# SolidWorksModel.net
KiCad netlist of a schematic drawn in EAGLE
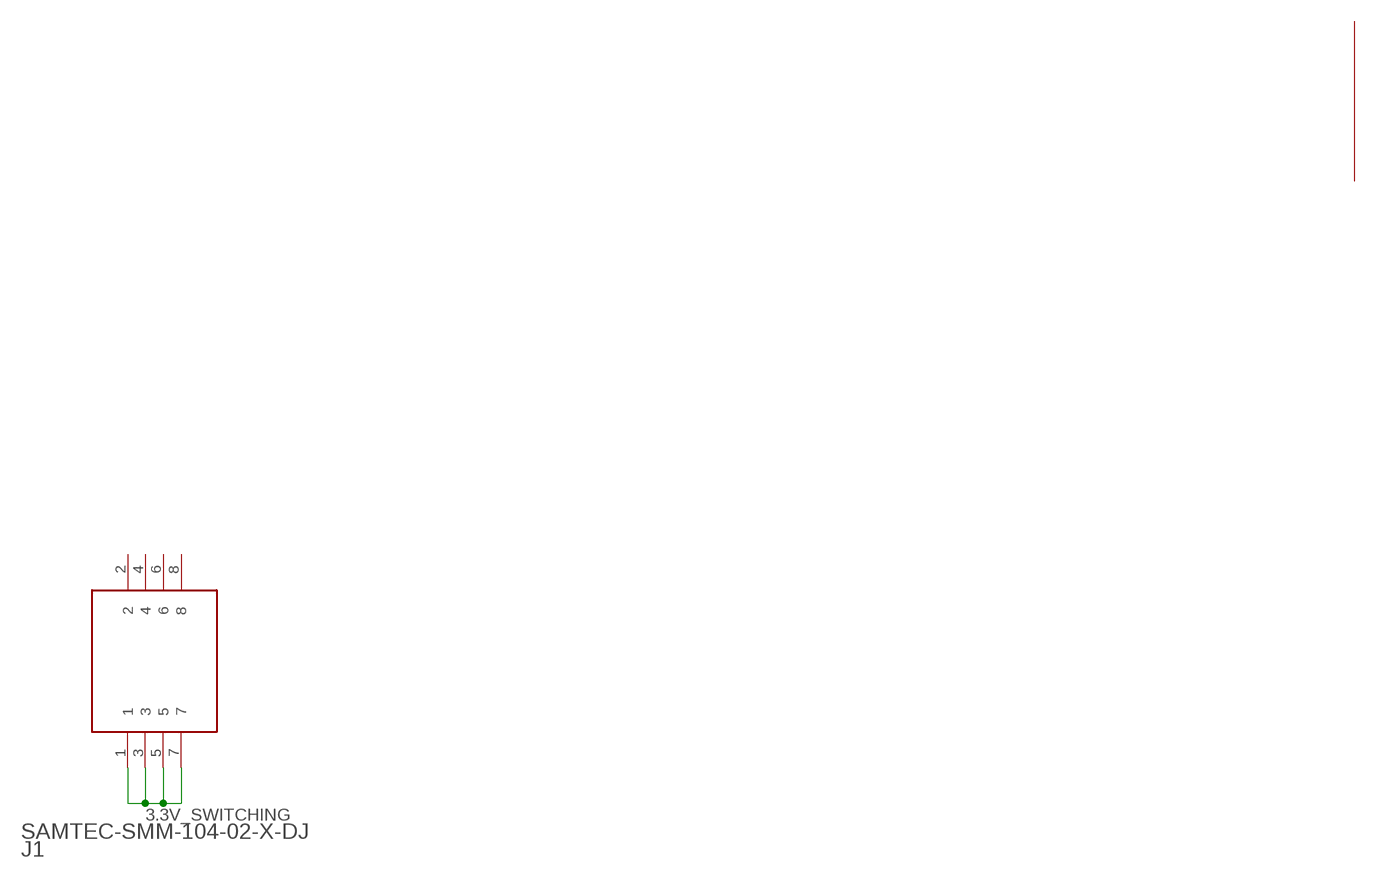
[diagram p0: schematic, sheet 3]
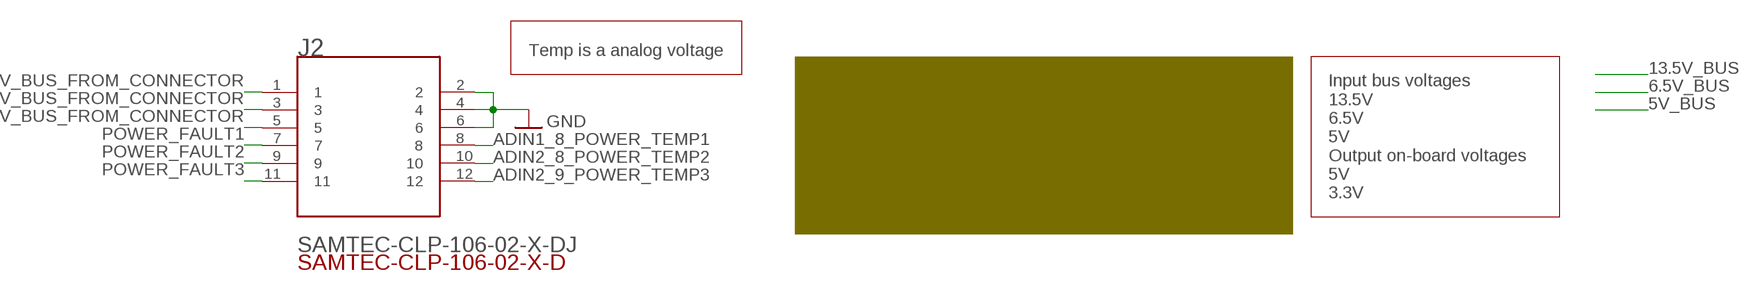
[diagram p1: schematic, sheet 4]
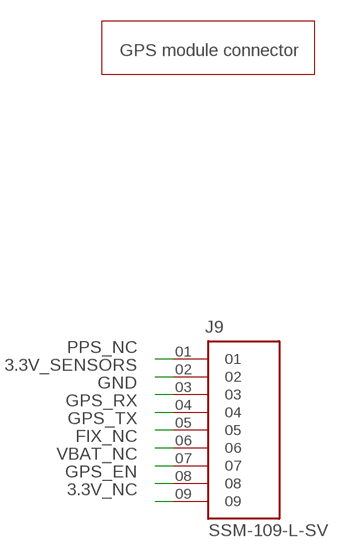
[diagram p2: schematic, sheet 7]
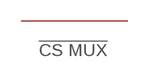
[diagram p3: schematic, sheet 10]
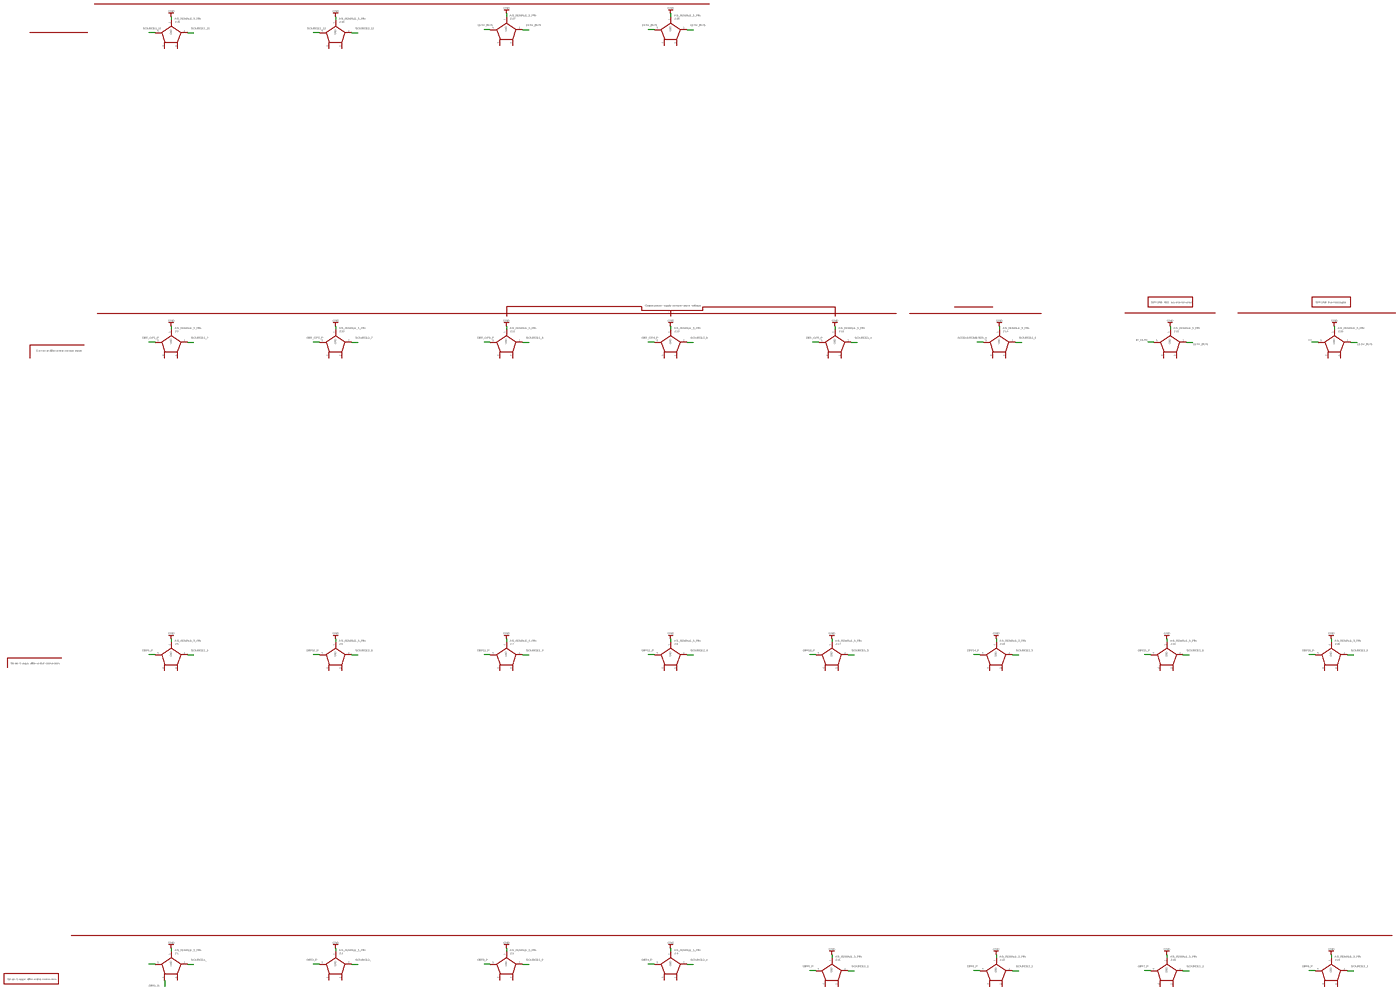
[diagram p4: schematic, sheet 11, overview]
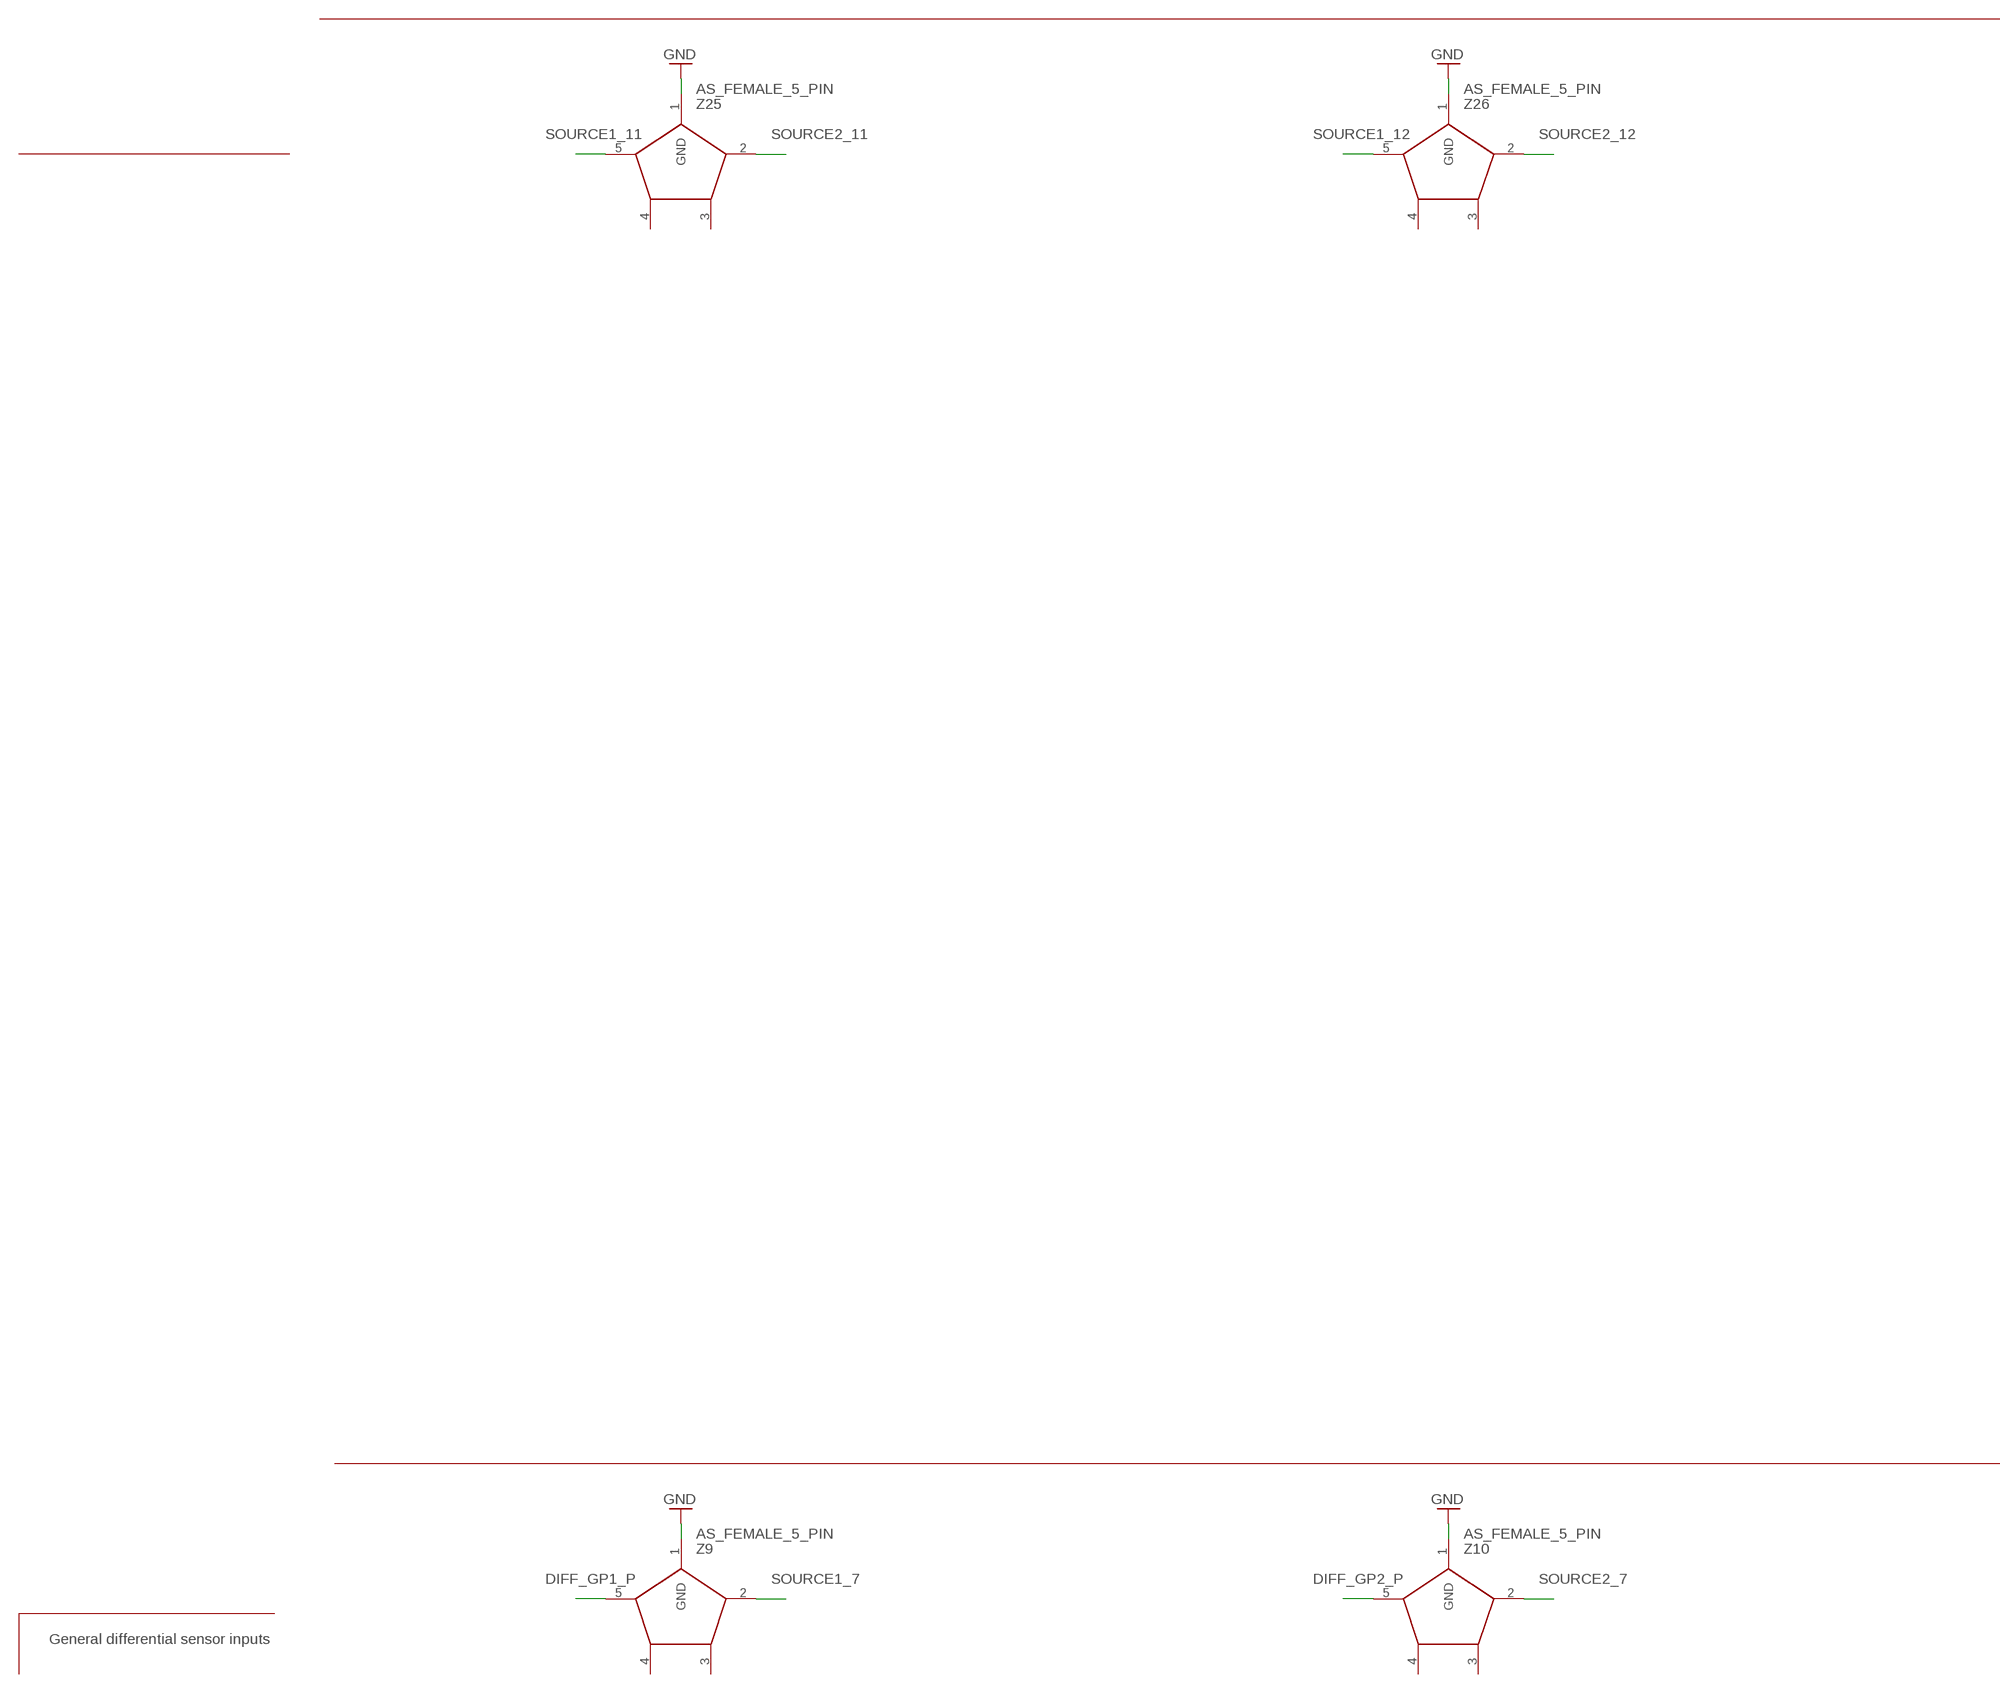
[diagram p5: schematic, sheet 11, part 1 of 6]
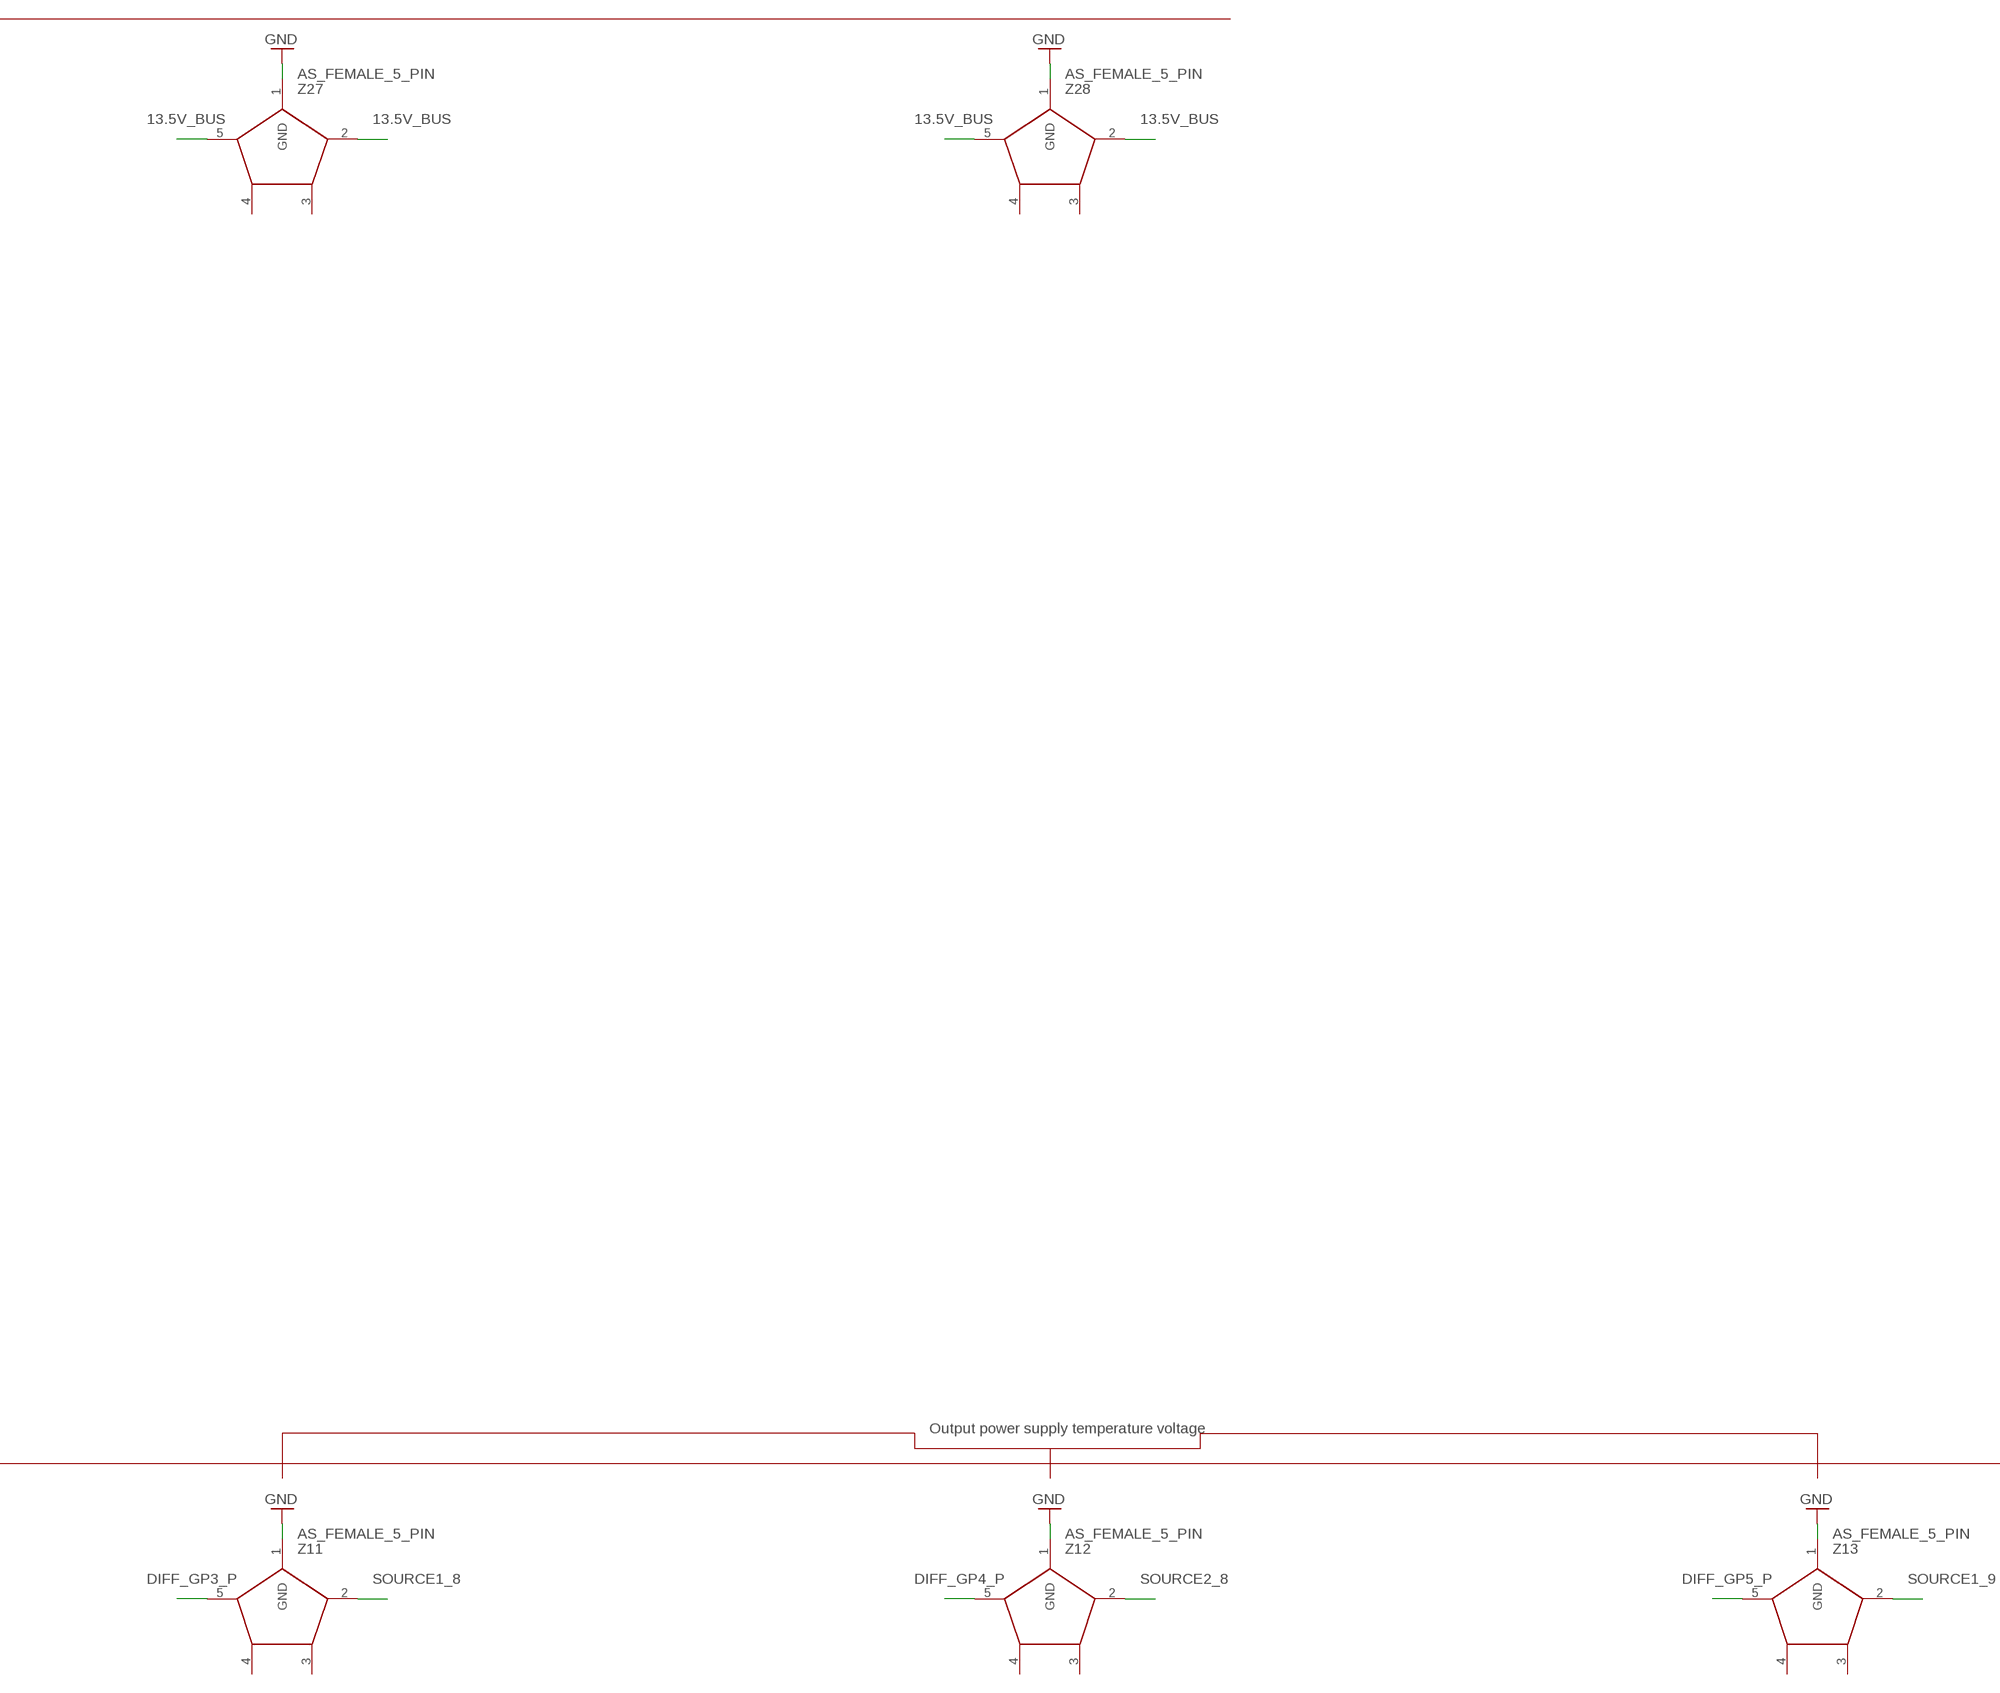
[diagram p6: schematic, sheet 11, part 2 of 6]
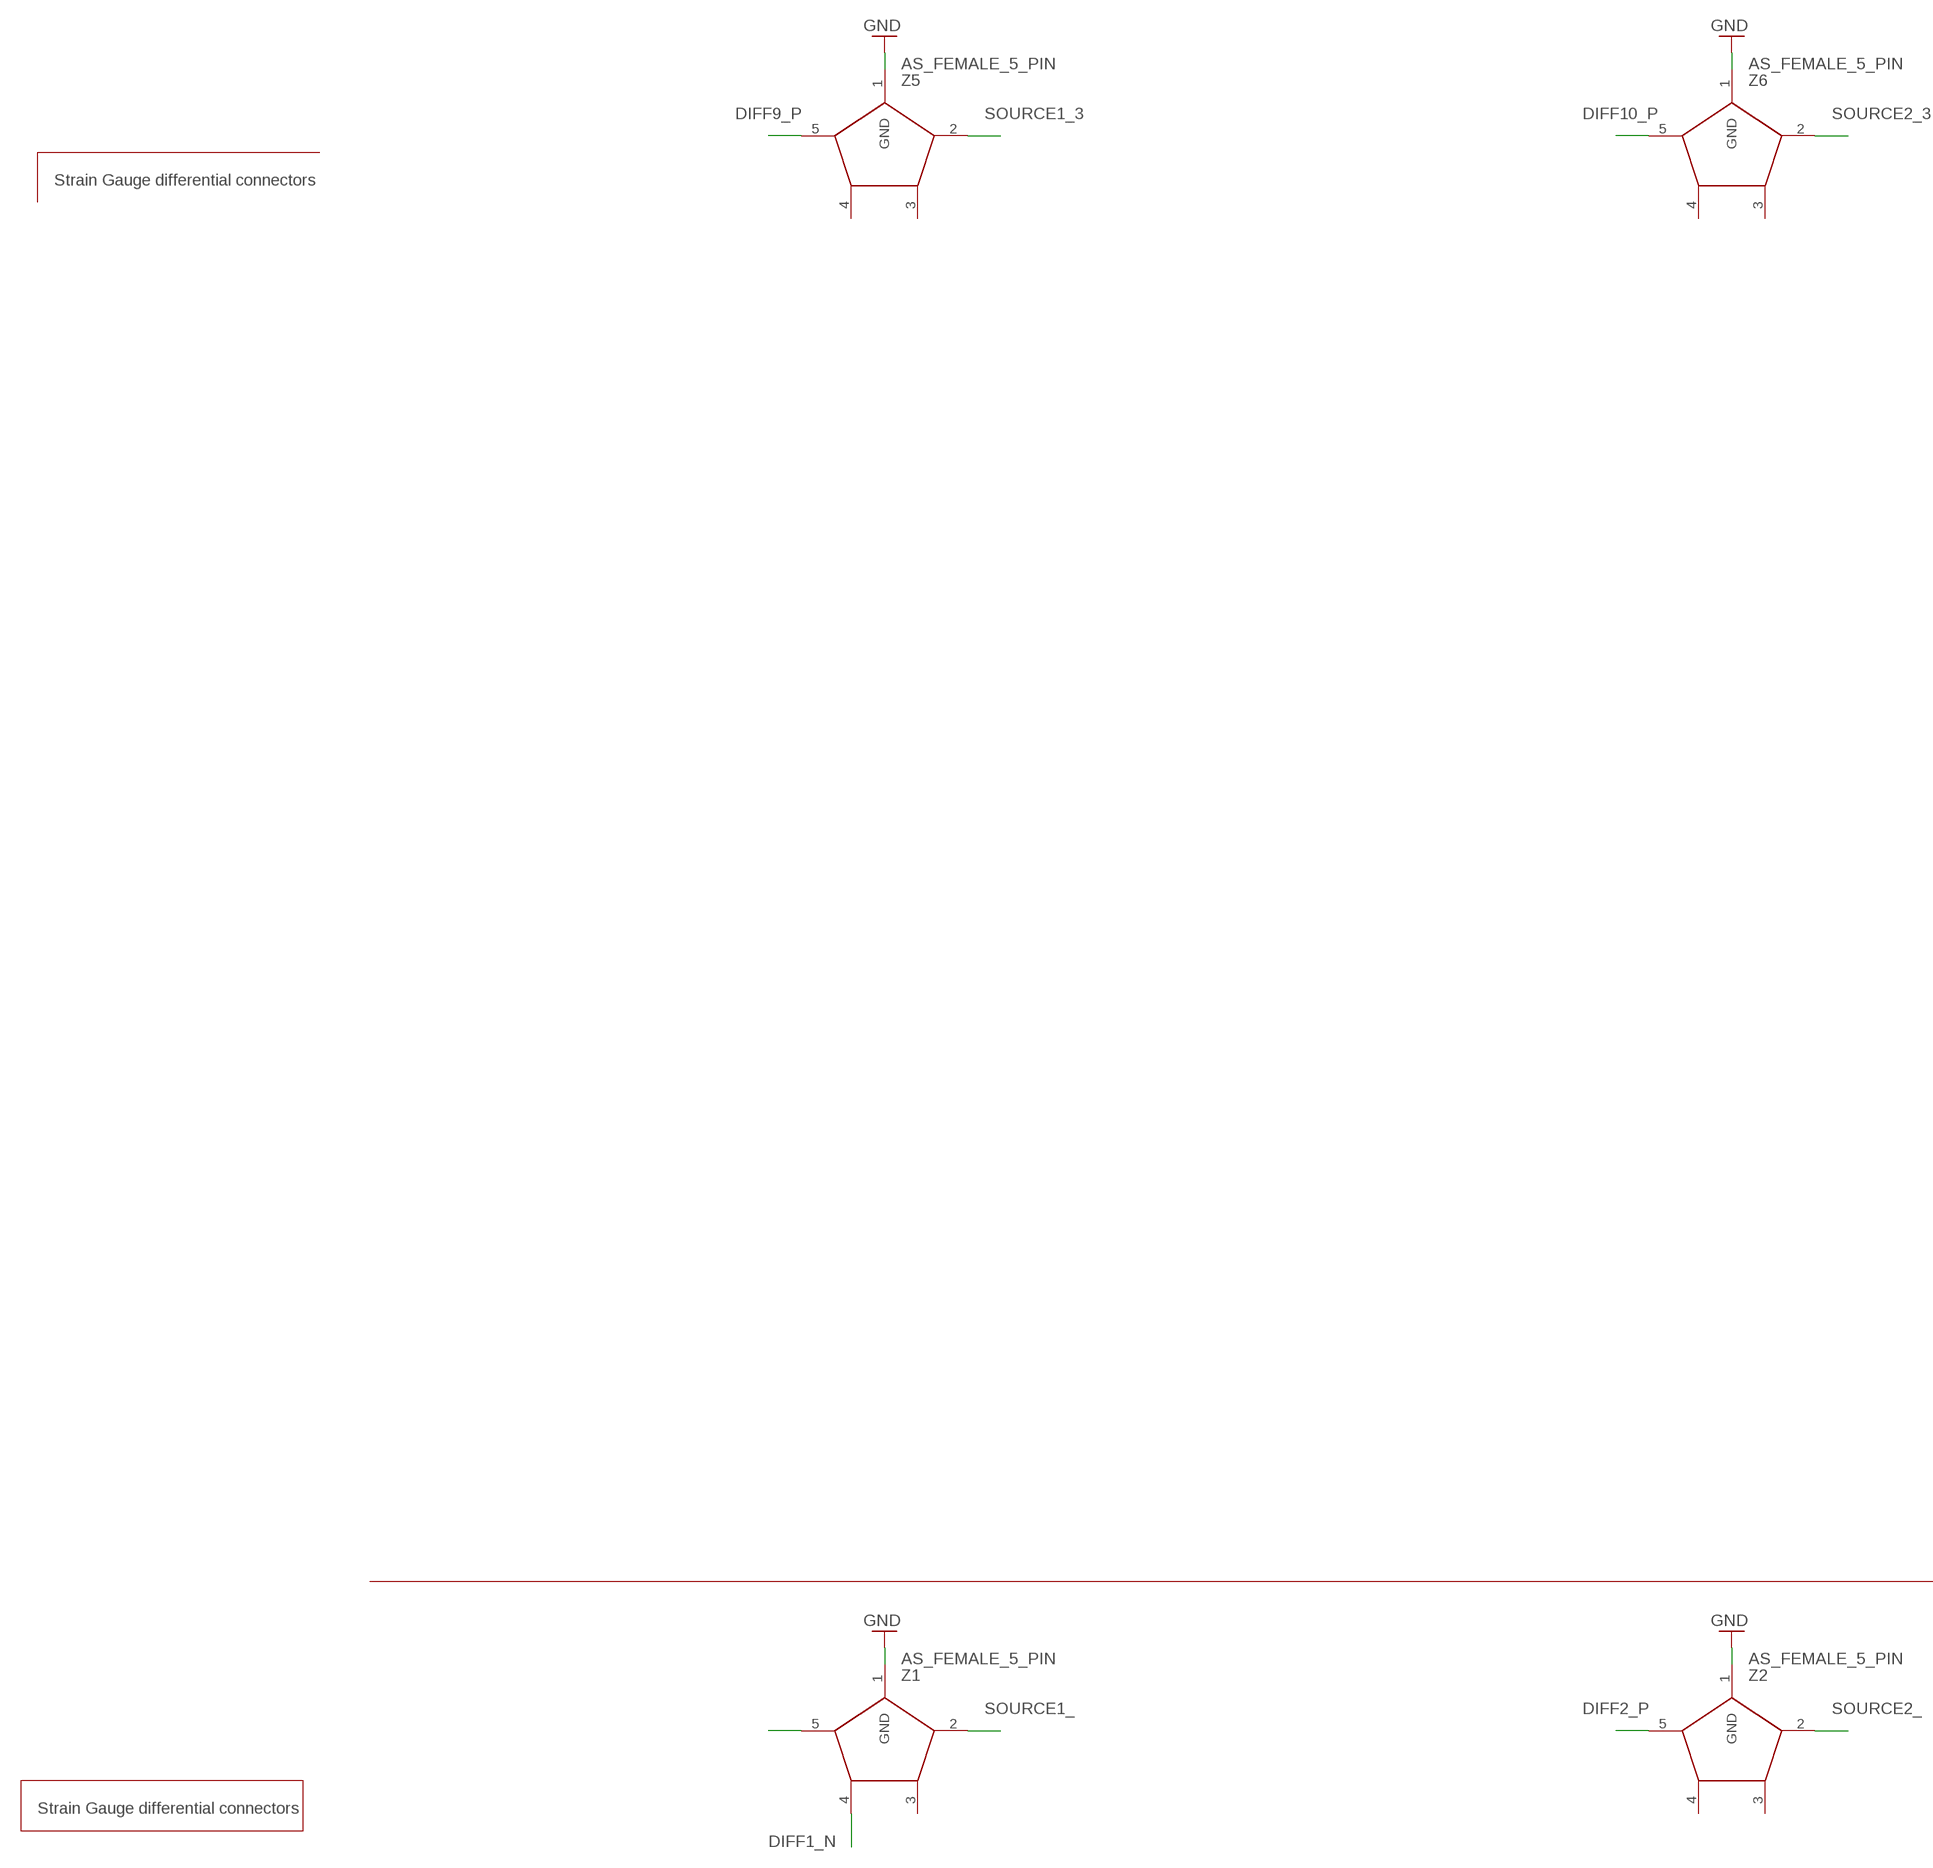
[diagram p7: schematic, sheet 11, part 3 of 6]
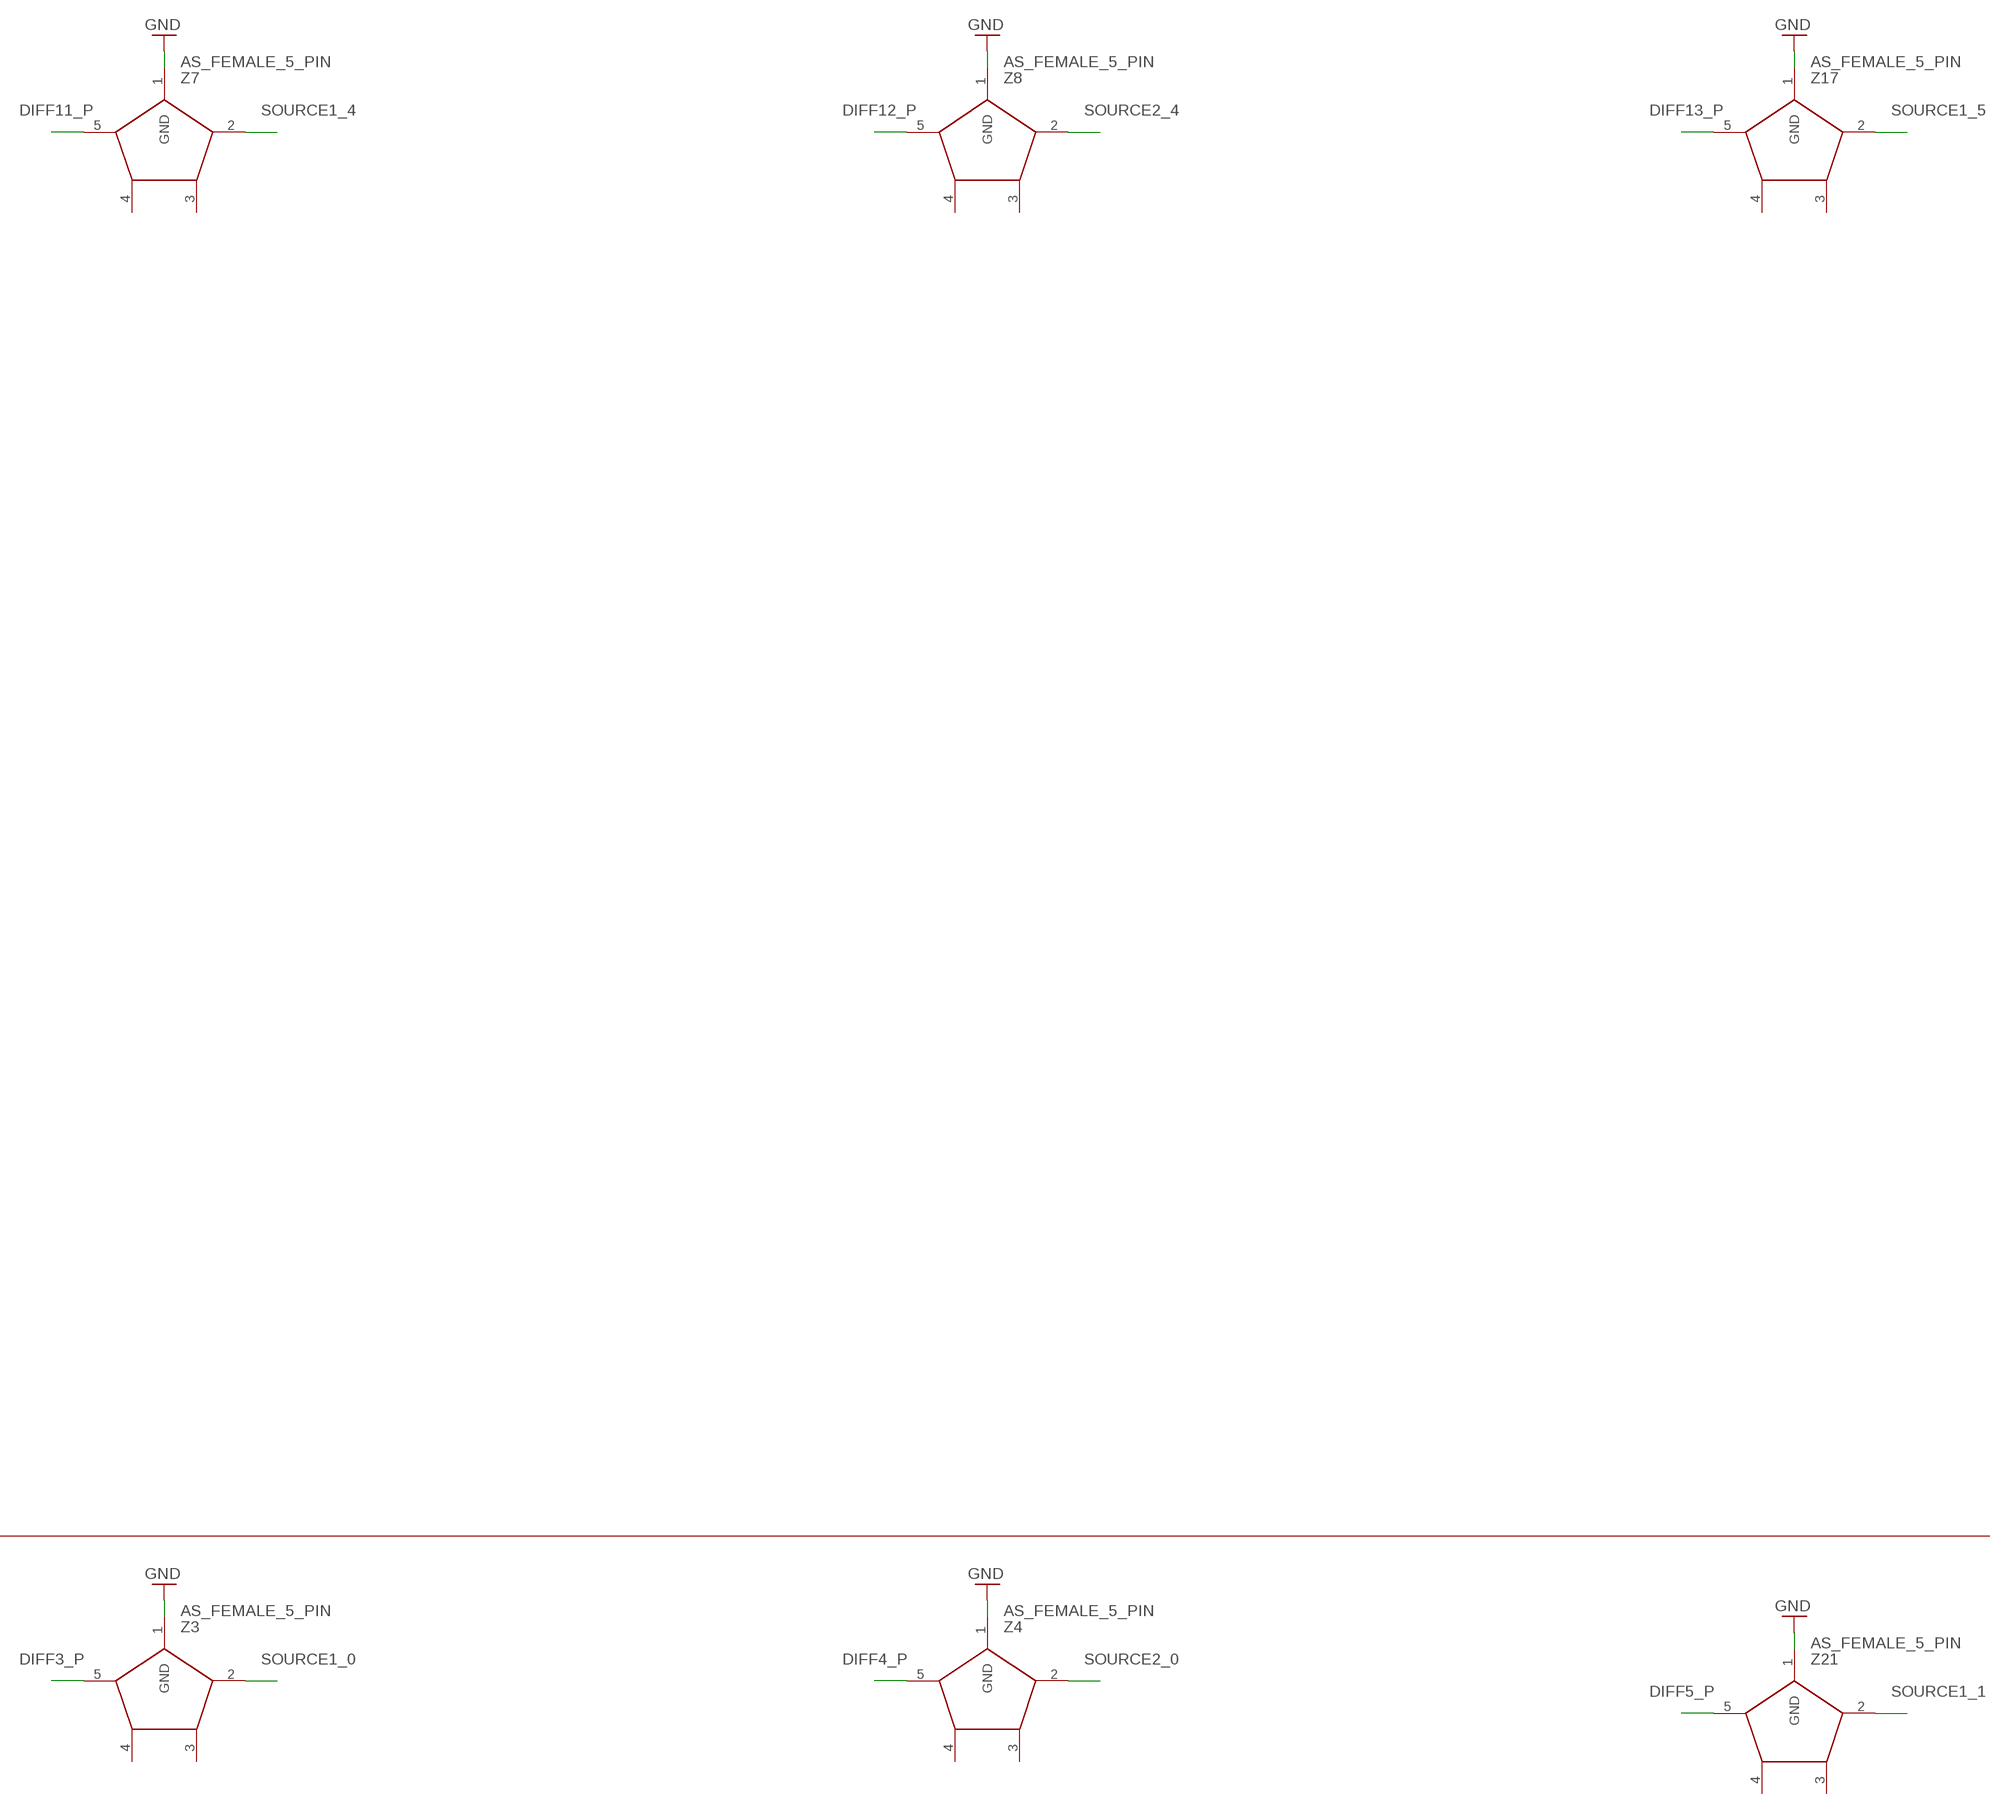
[diagram p8: schematic, sheet 11, part 4 of 6]
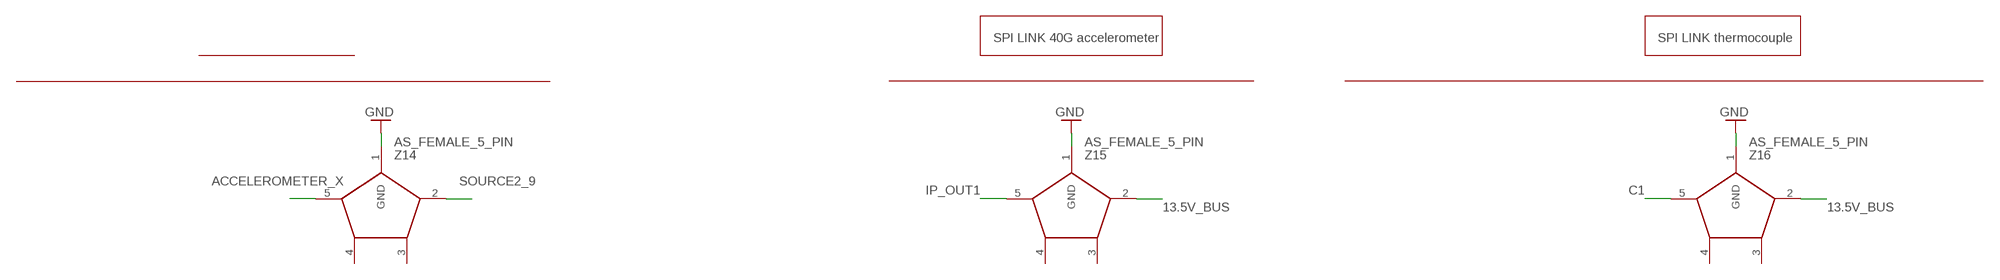
[diagram p9: schematic, sheet 11, part 5 of 6]
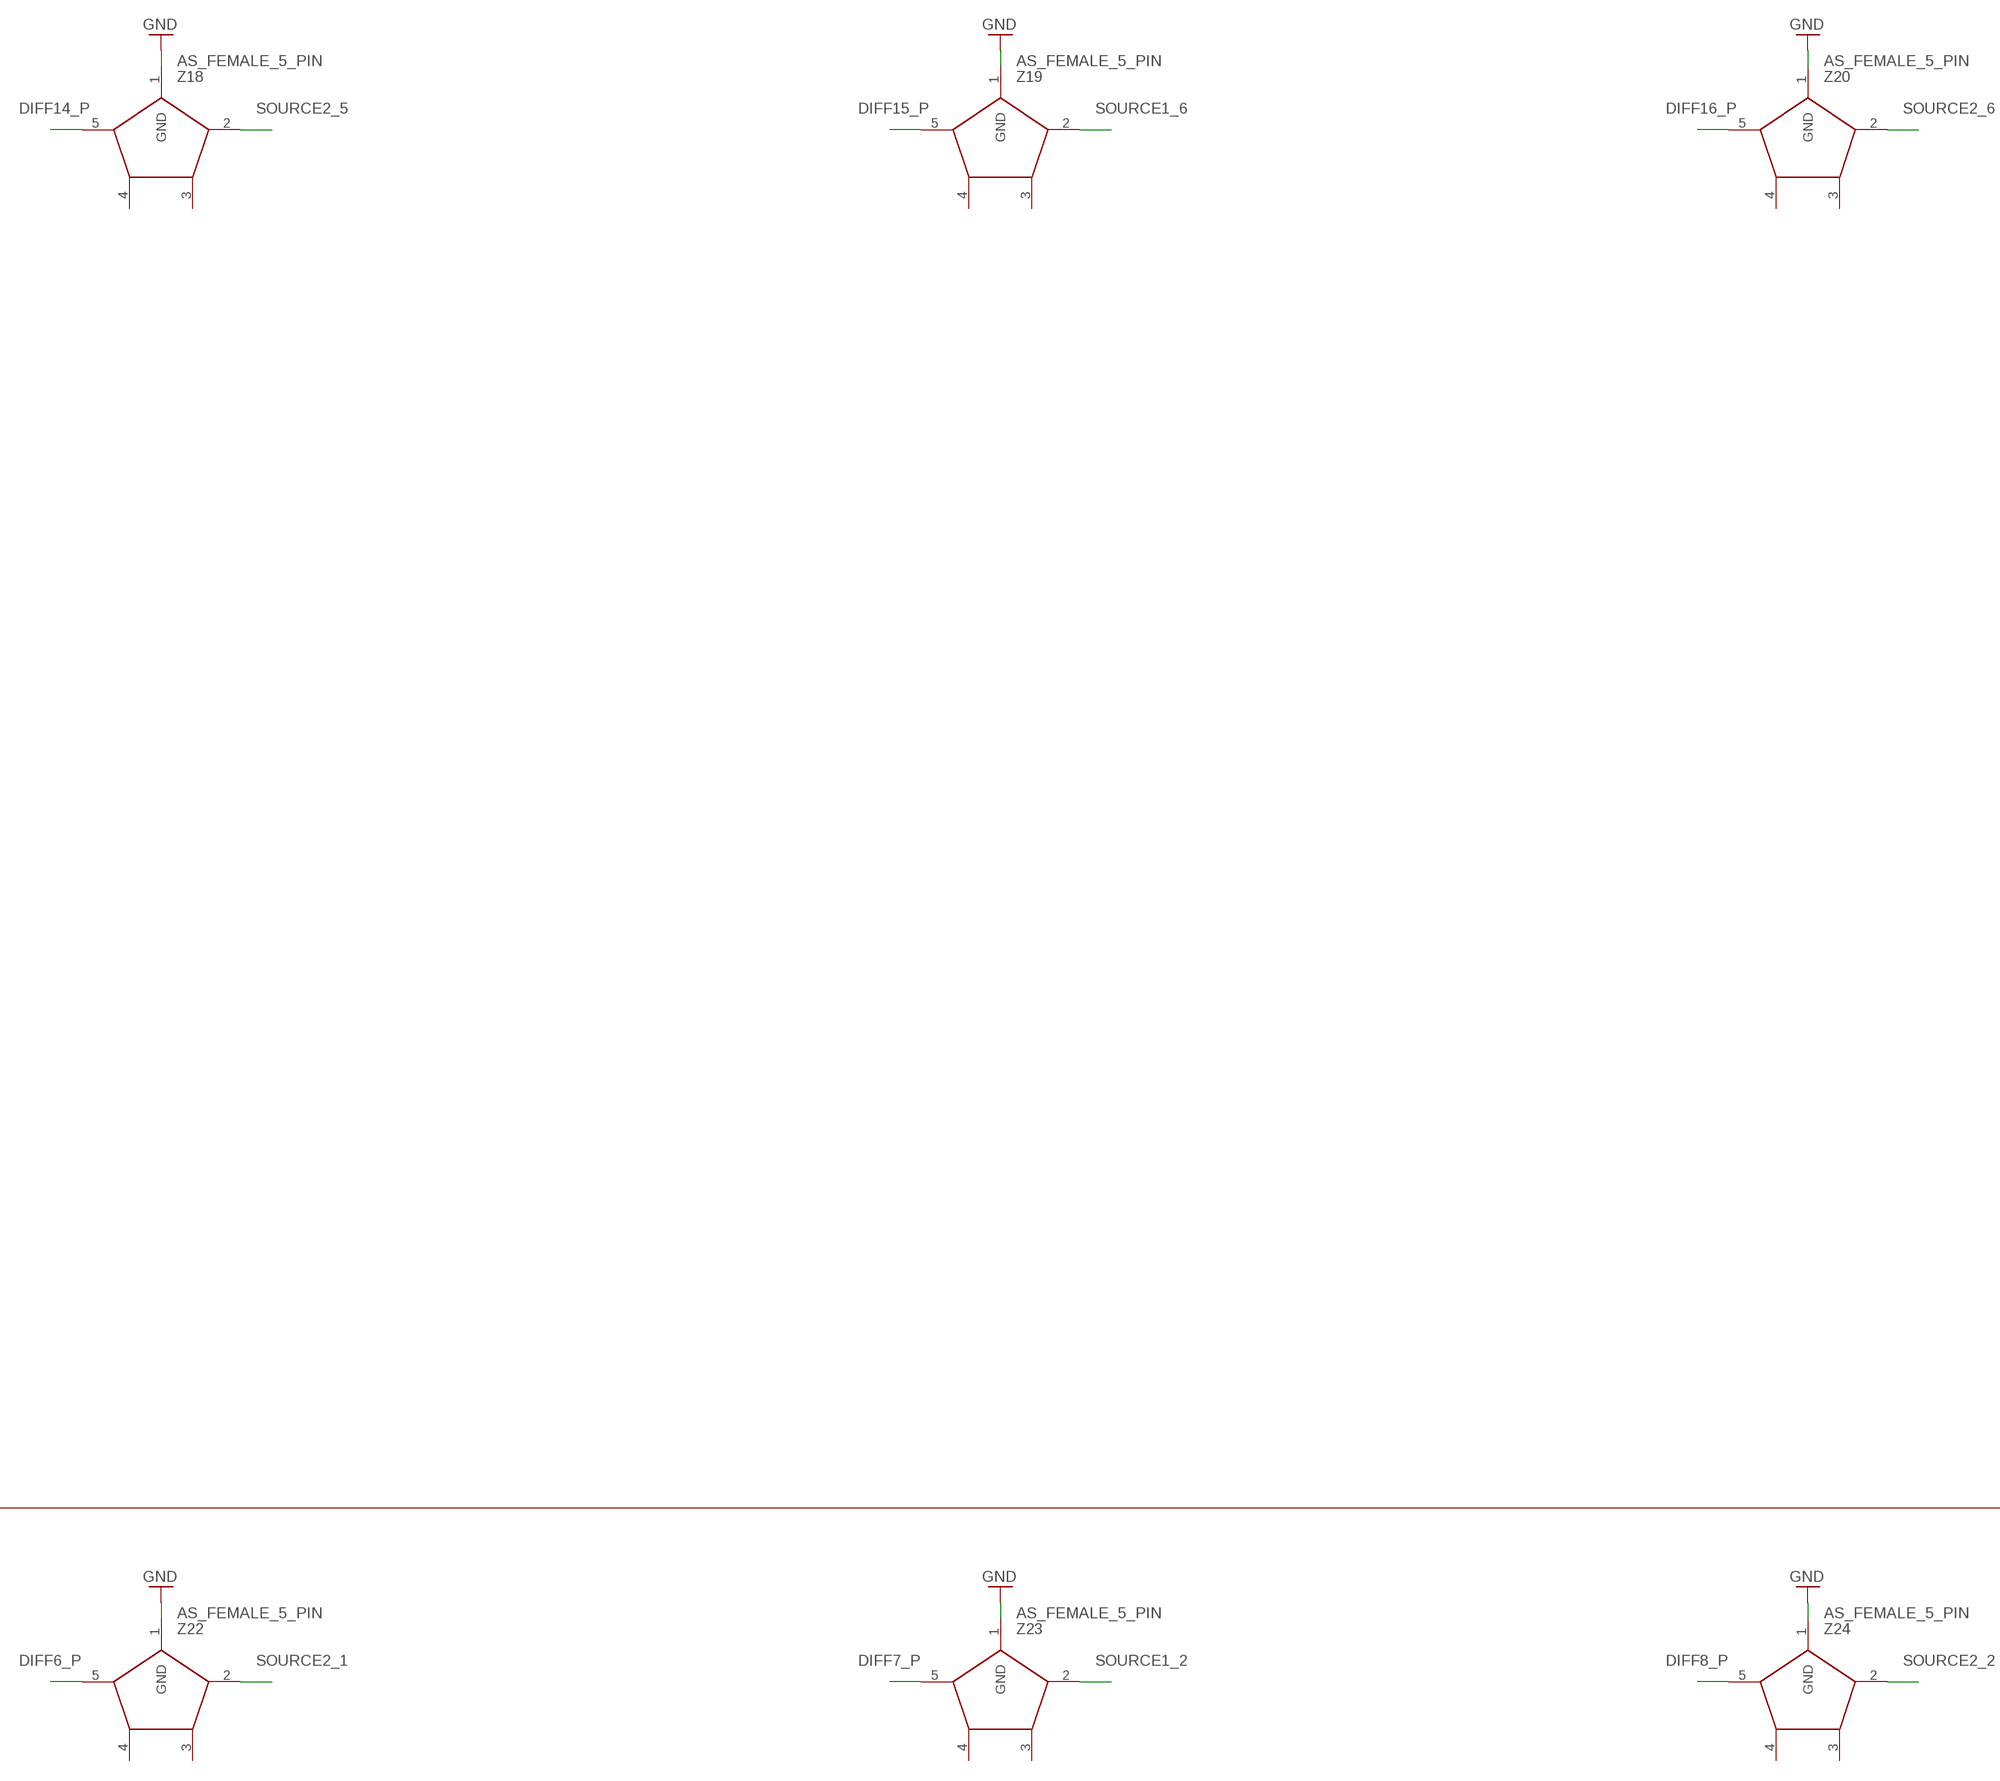
[diagram p10: schematic, sheet 11, part 6 of 6]
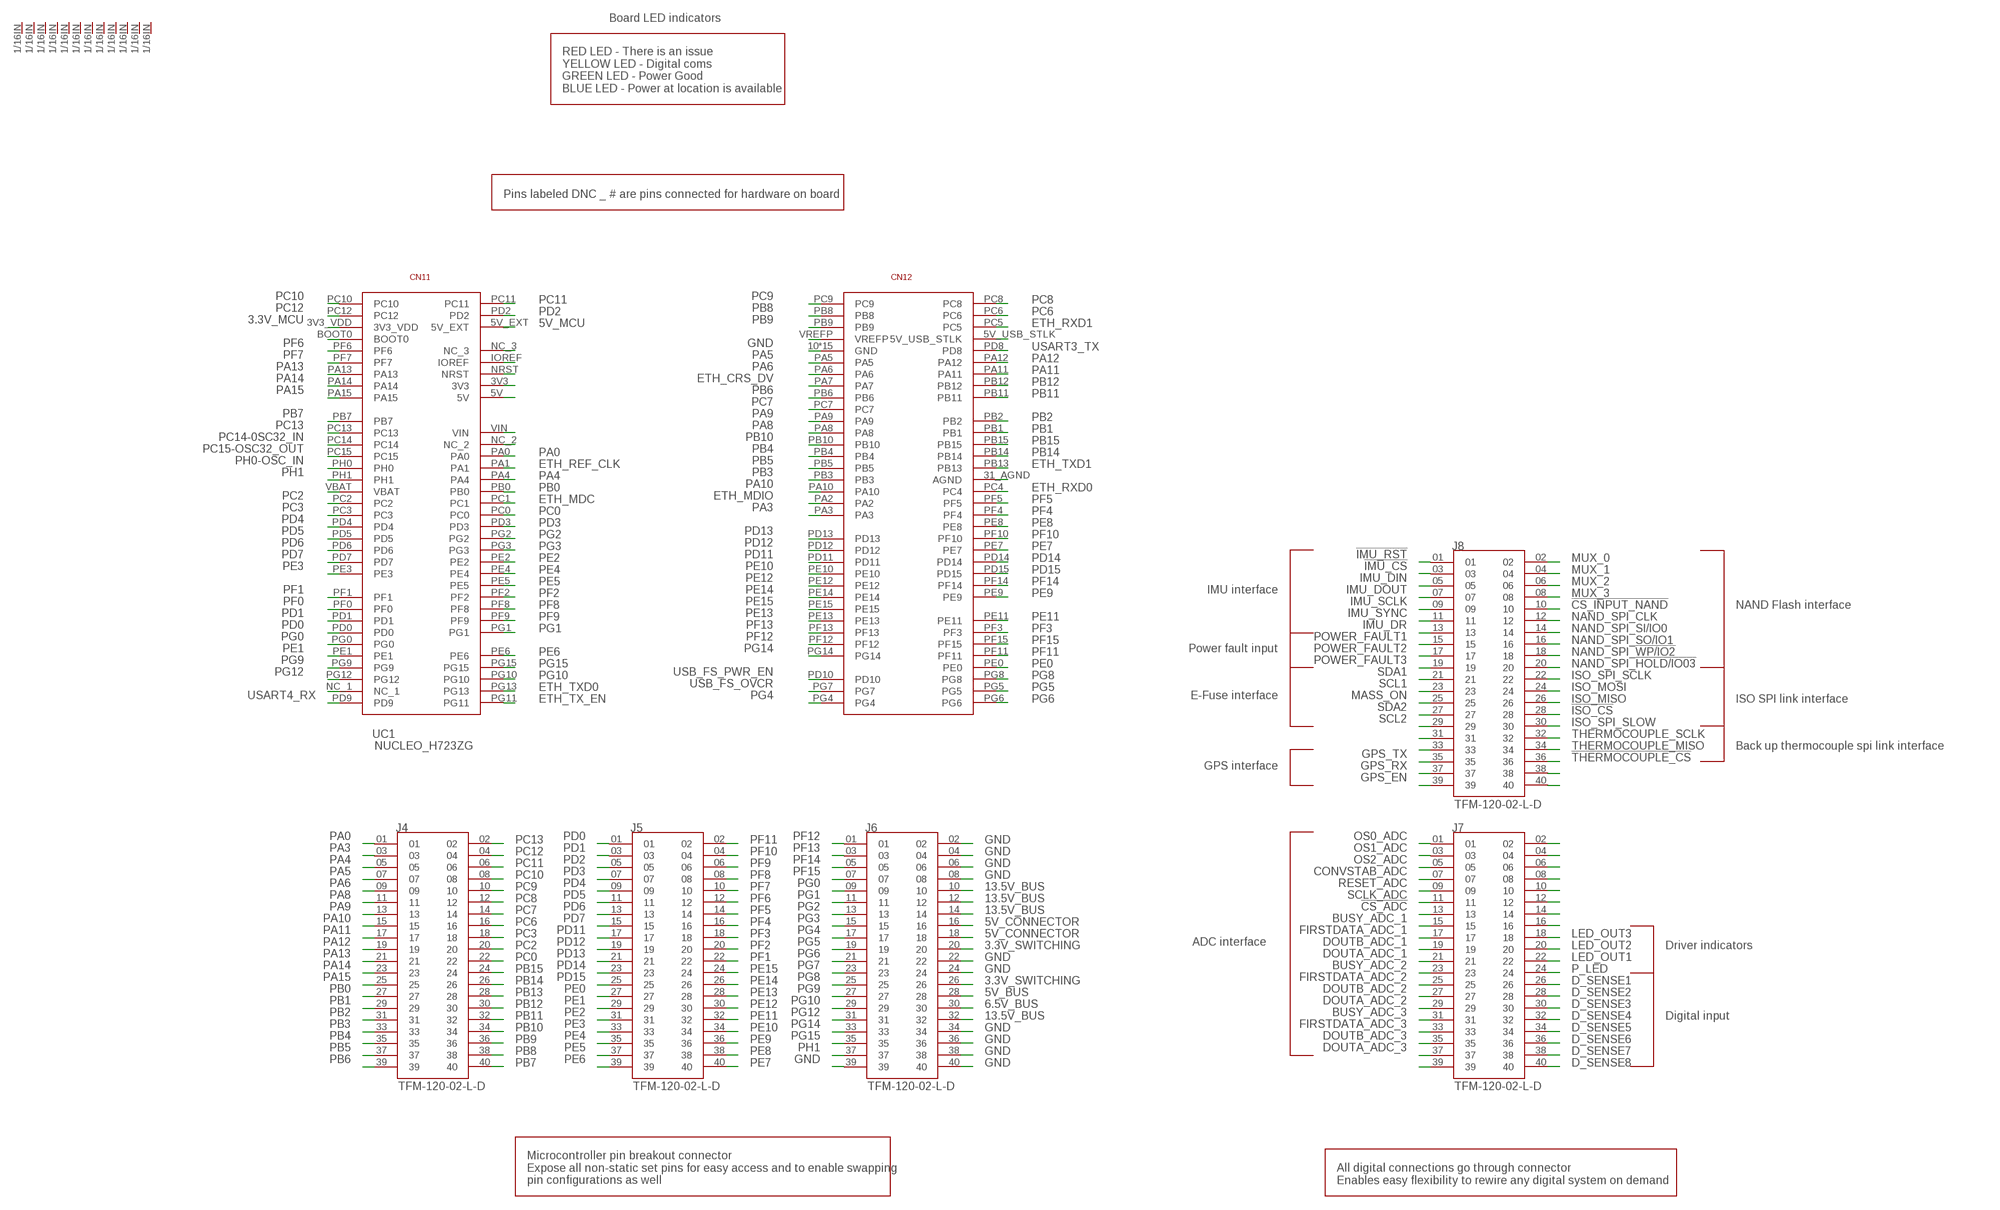
[diagram p11: schematic, sheet 12]

(export (version "E")
  (design (tool "Eeschema 10.0.6"))
  (components
    (comp (ref "J1")
      (value "SAMTEC-SMM-104-02-X-DJ")
      (footprint "eagle-import:SAMTEC-SMM-104-02-X-D")
      (libsource (lib "eagle-import") (part "SAMTEC-SMM-104-02-X-DJ"))
    )
    (comp (ref "J4")
      (value "TFM-120-02-L-D")
      (footprint "eagle-import:SAMTEC_TFM-120-02-L-D")
      (fields (field (name "MANUFACTURER") "Samtec"))
      (libsource (lib "eagle-import") (part "TFM-120-02-L-D"))
    )
    (comp (ref "J5")
      (value "TFM-120-02-L-D")
      (footprint "eagle-import:SAMTEC_TFM-120-02-L-D")
      (fields (field (name "MANUFACTURER") "Samtec"))
      (libsource (lib "eagle-import") (part "TFM-120-02-L-D"))
    )
    (comp (ref "J6")
      (value "TFM-120-02-L-D")
      (footprint "eagle-import:SAMTEC_TFM-120-02-L-D")
      (fields (field (name "MANUFACTURER") "Samtec"))
      (libsource (lib "eagle-import") (part "TFM-120-02-L-D"))
    )
    (comp (ref "J7")
      (value "TFM-120-02-L-D")
      (footprint "eagle-import:SAMTEC_TFM-120-02-L-D")
      (fields (field (name "MANUFACTURER") "Samtec"))
      (libsource (lib "eagle-import") (part "TFM-120-02-L-D"))
    )
    (comp (ref "J8")
      (value "TFM-120-02-L-D")
      (footprint "eagle-import:SAMTEC_TFM-120-02-L-D")
      (fields (field (name "MANUFACTURER") "Samtec"))
      (libsource (lib "eagle-import") (part "TFM-120-02-L-D"))
    )
    (comp (ref "U$1")
      (value "THROUGH_HOLE")
      (footprint "eagle-import:1_16TH_BOLT")
      (libsource (lib "eagle-import") (part "THROUGH_HOLE"))
    )
    (comp (ref "U$2")
      (value "THROUGH_HOLE")
      (footprint "eagle-import:1_16TH_BOLT")
      (libsource (lib "eagle-import") (part "THROUGH_HOLE"))
    )
    (comp (ref "U$3")
      (value "THROUGH_HOLE")
      (footprint "eagle-import:1_16TH_BOLT")
      (libsource (lib "eagle-import") (part "THROUGH_HOLE"))
    )
    (comp (ref "U$4")
      (value "THROUGH_HOLE")
      (footprint "eagle-import:1_16TH_BOLT")
      (libsource (lib "eagle-import") (part "THROUGH_HOLE"))
    )
    (comp (ref "U$5")
      (value "THROUGH_HOLE")
      (footprint "eagle-import:1_16TH_BOLT")
      (libsource (lib "eagle-import") (part "THROUGH_HOLE"))
    )
    (comp (ref "U$6")
      (value "THROUGH_HOLE")
      (footprint "eagle-import:1_16TH_BOLT")
      (libsource (lib "eagle-import") (part "THROUGH_HOLE"))
    )
    (comp (ref "U$7")
      (value "THROUGH_HOLE")
      (footprint "eagle-import:1_16TH_BOLT")
      (libsource (lib "eagle-import") (part "THROUGH_HOLE"))
    )
    (comp (ref "U$8")
      (value "THROUGH_HOLE")
      (footprint "eagle-import:1_16TH_BOLT")
      (libsource (lib "eagle-import") (part "THROUGH_HOLE"))
    )
    (comp (ref "U$9")
      (value "THROUGH_HOLE")
      (footprint "eagle-import:1_16TH_BOLT")
      (libsource (lib "eagle-import") (part "THROUGH_HOLE"))
    )
    (comp (ref "U$10")
      (value "THROUGH_HOLE")
      (footprint "eagle-import:1_16TH_BOLT")
      (libsource (lib "eagle-import") (part "THROUGH_HOLE"))
    )
    (comp (ref "U$11")
      (value "THROUGH_HOLE")
      (footprint "eagle-import:1_16TH_BOLT")
      (libsource (lib "eagle-import") (part "THROUGH_HOLE"))
    )
    (comp (ref "U$12")
      (value "THROUGH_HOLE")
      (footprint "eagle-import:1_16TH_BOLT")
      (libsource (lib "eagle-import") (part "THROUGH_HOLE"))
    )
    (comp (ref "UC1")
      (value "NUCLEO_H723ZG")
      (footprint "eagle-import:NUCLEO_H723ZG")
      (libsource (lib "eagle-import") (part "NUCLEO_H723ZG"))
    )
    (comp (ref "J2")
      (value "SAMTEC-CLP-106-02-X-DJ")
      (footprint "eagle-import:SAMTEC-CLP-106-02-X-D")
      (libsource (lib "eagle-import") (part "SAMTEC-CLP-106-02-X-DJ"))
    )
    (comp (ref "J9")
      (value "SSM-109-L-SV")
      (footprint "eagle-import:SAMTEC_SSM-109-L-SV")
      (fields (field (name "MANUFACTURER") "SAMTEC "))
      (libsource (lib "eagle-import") (part "SSM-109-L-SV"))
    )
    (comp (ref "Z1")
      (value "AS_FEMALE_5_PIN")
      (footprint "eagle-import:AS_FEMALE_5_PIN")
      (libsource (lib "eagle-import") (part "AS_FEMALE_5_PIN"))
    )
    (comp (ref "Z2")
      (value "AS_FEMALE_5_PIN")
      (footprint "eagle-import:AS_FEMALE_5_PIN")
      (libsource (lib "eagle-import") (part "AS_FEMALE_5_PIN"))
    )
    (comp (ref "Z3")
      (value "AS_FEMALE_5_PIN")
      (footprint "eagle-import:AS_FEMALE_5_PIN")
      (libsource (lib "eagle-import") (part "AS_FEMALE_5_PIN"))
    )
    (comp (ref "Z4")
      (value "AS_FEMALE_5_PIN")
      (footprint "eagle-import:AS_FEMALE_5_PIN")
      (libsource (lib "eagle-import") (part "AS_FEMALE_5_PIN"))
    )
    (comp (ref "Z5")
      (value "AS_FEMALE_5_PIN")
      (footprint "eagle-import:AS_FEMALE_5_PIN")
      (libsource (lib "eagle-import") (part "AS_FEMALE_5_PIN"))
    )
    (comp (ref "Z6")
      (value "AS_FEMALE_5_PIN")
      (footprint "eagle-import:AS_FEMALE_5_PIN")
      (libsource (lib "eagle-import") (part "AS_FEMALE_5_PIN"))
    )
    (comp (ref "Z7")
      (value "AS_FEMALE_5_PIN")
      (footprint "eagle-import:AS_FEMALE_5_PIN")
      (libsource (lib "eagle-import") (part "AS_FEMALE_5_PIN"))
    )
    (comp (ref "Z8")
      (value "AS_FEMALE_5_PIN")
      (footprint "eagle-import:AS_FEMALE_5_PIN")
      (libsource (lib "eagle-import") (part "AS_FEMALE_5_PIN"))
    )
    (comp (ref "Z9")
      (value "AS_FEMALE_5_PIN")
      (footprint "eagle-import:AS_FEMALE_5_PIN")
      (libsource (lib "eagle-import") (part "AS_FEMALE_5_PIN"))
    )
    (comp (ref "Z10")
      (value "AS_FEMALE_5_PIN")
      (footprint "eagle-import:AS_FEMALE_5_PIN")
      (libsource (lib "eagle-import") (part "AS_FEMALE_5_PIN"))
    )
    (comp (ref "Z11")
      (value "AS_FEMALE_5_PIN")
      (footprint "eagle-import:AS_FEMALE_5_PIN")
      (libsource (lib "eagle-import") (part "AS_FEMALE_5_PIN"))
    )
    (comp (ref "Z12")
      (value "AS_FEMALE_5_PIN")
      (footprint "eagle-import:AS_FEMALE_5_PIN")
      (libsource (lib "eagle-import") (part "AS_FEMALE_5_PIN"))
    )
    (comp (ref "Z13")
      (value "AS_FEMALE_5_PIN")
      (footprint "eagle-import:AS_FEMALE_5_PIN")
      (libsource (lib "eagle-import") (part "AS_FEMALE_5_PIN"))
    )
    (comp (ref "Z14")
      (value "AS_FEMALE_5_PIN")
      (footprint "eagle-import:AS_FEMALE_5_PIN")
      (libsource (lib "eagle-import") (part "AS_FEMALE_5_PIN"))
    )
    (comp (ref "Z15")
      (value "AS_FEMALE_5_PIN")
      (footprint "eagle-import:AS_FEMALE_5_PIN")
      (libsource (lib "eagle-import") (part "AS_FEMALE_5_PIN"))
    )
    (comp (ref "Z16")
      (value "AS_FEMALE_5_PIN")
      (footprint "eagle-import:AS_FEMALE_5_PIN")
      (libsource (lib "eagle-import") (part "AS_FEMALE_5_PIN"))
    )
    (comp (ref "Z17")
      (value "AS_FEMALE_5_PIN")
      (footprint "eagle-import:AS_FEMALE_5_PIN")
      (libsource (lib "eagle-import") (part "AS_FEMALE_5_PIN"))
    )
    (comp (ref "Z18")
      (value "AS_FEMALE_5_PIN")
      (footprint "eagle-import:AS_FEMALE_5_PIN")
      (libsource (lib "eagle-import") (part "AS_FEMALE_5_PIN"))
    )
    (comp (ref "Z19")
      (value "AS_FEMALE_5_PIN")
      (footprint "eagle-import:AS_FEMALE_5_PIN")
      (libsource (lib "eagle-import") (part "AS_FEMALE_5_PIN"))
    )
    (comp (ref "Z20")
      (value "AS_FEMALE_5_PIN")
      (footprint "eagle-import:AS_FEMALE_5_PIN")
      (libsource (lib "eagle-import") (part "AS_FEMALE_5_PIN"))
    )
    (comp (ref "Z21")
      (value "AS_FEMALE_5_PIN")
      (footprint "eagle-import:AS_FEMALE_5_PIN")
      (libsource (lib "eagle-import") (part "AS_FEMALE_5_PIN"))
    )
    (comp (ref "Z22")
      (value "AS_FEMALE_5_PIN")
      (footprint "eagle-import:AS_FEMALE_5_PIN")
      (libsource (lib "eagle-import") (part "AS_FEMALE_5_PIN"))
    )
    (comp (ref "Z23")
      (value "AS_FEMALE_5_PIN")
      (footprint "eagle-import:AS_FEMALE_5_PIN")
      (libsource (lib "eagle-import") (part "AS_FEMALE_5_PIN"))
    )
    (comp (ref "Z24")
      (value "AS_FEMALE_5_PIN")
      (footprint "eagle-import:AS_FEMALE_5_PIN")
      (libsource (lib "eagle-import") (part "AS_FEMALE_5_PIN"))
    )
    (comp (ref "Z25")
      (value "AS_FEMALE_5_PIN")
      (footprint "eagle-import:AS_FEMALE_5_PIN")
      (libsource (lib "eagle-import") (part "AS_FEMALE_5_PIN"))
    )
    (comp (ref "Z26")
      (value "AS_FEMALE_5_PIN")
      (footprint "eagle-import:AS_FEMALE_5_PIN")
      (libsource (lib "eagle-import") (part "AS_FEMALE_5_PIN"))
    )
    (comp (ref "Z27")
      (value "AS_FEMALE_5_PIN")
      (footprint "eagle-import:AS_FEMALE_5_PIN")
      (libsource (lib "eagle-import") (part "AS_FEMALE_5_PIN"))
    )
    (comp (ref "Z28")
      (value "AS_FEMALE_5_PIN")
      (footprint "eagle-import:AS_FEMALE_5_PIN")
      (libsource (lib "eagle-import") (part "AS_FEMALE_5_PIN"))
    )
  )
  (nets
    (net (code "1") (name "3.3V_MCU") (class "Default")
      (node (ref "UC1") (pin "3V3_VDD") (pinfunction "3V3_VDD_3V3_VDD") (pintype "passive"))
    )
    (net (code "2") (name "3.3V_NC") (class "Default")
      (node (ref "J9") (pin "09") (pinfunction "09_09") (pintype "passive"))
    )
    (net (code "3") (name "3.3V_SENSORS") (class "Default")
      (node (ref "J9") (pin "02") (pinfunction "02_02") (pintype "passive"))
    )
    (net (code "4") (name "3.3V_SWITCHING") (class "Default")
      (node (ref "J1") (pin "1") (pinfunction "1_1") (pintype "passive"))
      (node (ref "J1") (pin "3") (pinfunction "3_3") (pintype "passive"))
      (node (ref "J1") (pin "5") (pinfunction "5_5") (pintype "passive"))
      (node (ref "J1") (pin "7") (pinfunction "7_7") (pintype "passive"))
      (node (ref "J6") (pin "20") (pinfunction "20_20") (pintype "passive"))
      (node (ref "J6") (pin "26") (pinfunction "26_26") (pintype "passive"))
    )
    (net (code "5") (name "5V_BUS") (class "Default")
      (node (ref "J6") (pin "28") (pinfunction "28_28") (pintype "passive"))
    )
    (net (code "6") (name "5V_BUS_FROM_CONNECTOR") (class "Default")
      (node (ref "J2") (pin "5") (pinfunction "5_5") (pintype "passive"))
    )
    (net (code "7") (name "5V_CONNECTOR") (class "Default")
      (node (ref "J6") (pin "16") (pinfunction "16_16") (pintype "passive"))
      (node (ref "J6") (pin "18") (pinfunction "18_18") (pintype "passive"))
    )
    (net (code "8") (name "5V_MCU") (class "Default")
      (node (ref "UC1") (pin "5V_EXT") (pinfunction "5V_EXT_5V_EXT") (pintype "passive"))
    )
    (net (code "9") (name "6.5V_BUS") (class "Default")
      (node (ref "J6") (pin "30") (pinfunction "30_30") (pintype "passive"))
    )
    (net (code "10") (name "6.5V_BUS_FROM_CONNECTOR") (class "Default")
      (node (ref "J2") (pin "3") (pinfunction "3_3") (pintype "passive"))
    )
    (net (code "11") (name "13.5V_BUS") (class "Default")
      (node (ref "J6") (pin "10") (pinfunction "10_10") (pintype "passive"))
      (node (ref "J6") (pin "12") (pinfunction "12_12") (pintype "passive"))
      (node (ref "J6") (pin "14") (pinfunction "14_14") (pintype "passive"))
      (node (ref "J6") (pin "32") (pinfunction "32_32") (pintype "passive"))
      (node (ref "Z15") (pin "2") (pinfunction "1_2") (pintype "bidirectional"))
      (node (ref "Z16") (pin "2") (pinfunction "1_2") (pintype "bidirectional"))
      (node (ref "Z27") (pin "2") (pinfunction "1_2") (pintype "bidirectional"))
      (node (ref "Z27") (pin "5") (pinfunction "4_5") (pintype "bidirectional"))
      (node (ref "Z28") (pin "2") (pinfunction "1_2") (pintype "bidirectional"))
      (node (ref "Z28") (pin "5") (pinfunction "4_5") (pintype "bidirectional"))
    )
    (net (code "12") (name "14V_BUS_FROM_CONNECTOR") (class "Default")
      (node (ref "J2") (pin "1") (pinfunction "1_1") (pintype "passive"))
    )
    (net (code "13") (name "ACCELEROMETER_X") (class "Default")
      (node (ref "Z14") (pin "5") (pinfunction "4_5") (pintype "bidirectional"))
    )
    (net (code "14") (name "ADIN1_8_POWER_TEMP1") (class "Default")
      (node (ref "J2") (pin "8") (pinfunction "8_8") (pintype "passive"))
    )
    (net (code "15") (name "ADIN2_8_POWER_TEMP2") (class "Default")
      (node (ref "J2") (pin "10") (pinfunction "10_10") (pintype "passive"))
    )
    (net (code "16") (name "ADIN2_9_POWER_TEMP3") (class "Default")
      (node (ref "J2") (pin "12") (pinfunction "12_12") (pintype "passive"))
    )
    (net (code "17") (name "BUSY_ADC_1") (class "Default")
      (node (ref "J7") (pin "15") (pinfunction "15_15") (pintype "passive"))
    )
    (net (code "18") (name "BUSY_ADC_2") (class "Default")
      (node (ref "J7") (pin "23") (pinfunction "23_23") (pintype "passive"))
    )
    (net (code "19") (name "BUSY_ADC_3") (class "Default")
      (node (ref "J7") (pin "31") (pinfunction "31_31") (pintype "passive"))
    )
    (net (code "20") (name "C1") (class "Default")
      (node (ref "Z16") (pin "5") (pinfunction "4_5") (pintype "bidirectional"))
    )
    (net (code "21") (name "CONVSTAB_ADC") (class "Default")
      (node (ref "J7") (pin "07") (pinfunction "07_07") (pintype "passive"))
    )
    (net (code "22") (name "DIFF1_N") (class "Default")
      (node (ref "Z1") (pin "4") (pinfunction "3_4") (pintype "bidirectional"))
    )
    (net (code "23") (name "DIFF2_P") (class "Default")
      (node (ref "Z2") (pin "5") (pinfunction "4_5") (pintype "bidirectional"))
    )
    (net (code "24") (name "DIFF3_P") (class "Default")
      (node (ref "Z3") (pin "5") (pinfunction "4_5") (pintype "bidirectional"))
    )
    (net (code "25") (name "DIFF4_P") (class "Default")
      (node (ref "Z4") (pin "5") (pinfunction "4_5") (pintype "bidirectional"))
    )
    (net (code "26") (name "DIFF5_P") (class "Default")
      (node (ref "Z21") (pin "5") (pinfunction "4_5") (pintype "bidirectional"))
    )
    (net (code "27") (name "DIFF6_P") (class "Default")
      (node (ref "Z22") (pin "5") (pinfunction "4_5") (pintype "bidirectional"))
    )
    (net (code "28") (name "DIFF7_P") (class "Default")
      (node (ref "Z23") (pin "5") (pinfunction "4_5") (pintype "bidirectional"))
    )
    (net (code "29") (name "DIFF8_P") (class "Default")
      (node (ref "Z24") (pin "5") (pinfunction "4_5") (pintype "bidirectional"))
    )
    (net (code "30") (name "DIFF9_P") (class "Default")
      (node (ref "Z5") (pin "5") (pinfunction "4_5") (pintype "bidirectional"))
    )
    (net (code "31") (name "DIFF10_P") (class "Default")
      (node (ref "Z6") (pin "5") (pinfunction "4_5") (pintype "bidirectional"))
    )
    (net (code "32") (name "DIFF11_P") (class "Default")
      (node (ref "Z7") (pin "5") (pinfunction "4_5") (pintype "bidirectional"))
    )
    (net (code "33") (name "DIFF12_P") (class "Default")
      (node (ref "Z8") (pin "5") (pinfunction "4_5") (pintype "bidirectional"))
    )
    (net (code "34") (name "DIFF13_P") (class "Default")
      (node (ref "Z17") (pin "5") (pinfunction "4_5") (pintype "bidirectional"))
    )
    (net (code "35") (name "DIFF14_P") (class "Default")
      (node (ref "Z18") (pin "5") (pinfunction "4_5") (pintype "bidirectional"))
    )
    (net (code "36") (name "DIFF15_P") (class "Default")
      (node (ref "Z19") (pin "5") (pinfunction "4_5") (pintype "bidirectional"))
    )
    (net (code "37") (name "DIFF16_P") (class "Default")
      (node (ref "Z20") (pin "5") (pinfunction "4_5") (pintype "bidirectional"))
    )
    (net (code "38") (name "DIFF_GP1_P") (class "Default")
      (node (ref "Z9") (pin "5") (pinfunction "4_5") (pintype "bidirectional"))
    )
    (net (code "39") (name "DIFF_GP2_P") (class "Default")
      (node (ref "Z10") (pin "5") (pinfunction "4_5") (pintype "bidirectional"))
    )
    (net (code "40") (name "DIFF_GP3_P") (class "Default")
      (node (ref "Z11") (pin "5") (pinfunction "4_5") (pintype "bidirectional"))
    )
    (net (code "41") (name "DIFF_GP4_P") (class "Default")
      (node (ref "Z12") (pin "5") (pinfunction "4_5") (pintype "bidirectional"))
    )
    (net (code "42") (name "DIFF_GP5_P") (class "Default")
      (node (ref "Z13") (pin "5") (pinfunction "4_5") (pintype "bidirectional"))
    )
    (net (code "43") (name "DOUTA_ADC_1") (class "Default")
      (node (ref "J7") (pin "21") (pinfunction "21_21") (pintype "passive"))
    )
    (net (code "44") (name "DOUTA_ADC_2") (class "Default")
      (node (ref "J7") (pin "29") (pinfunction "29_29") (pintype "passive"))
    )
    (net (code "45") (name "DOUTA_ADC_3") (class "Default")
      (node (ref "J7") (pin "37") (pinfunction "37_37") (pintype "passive"))
    )
    (net (code "46") (name "DOUTB_ADC_1") (class "Default")
      (node (ref "J7") (pin "19") (pinfunction "19_19") (pintype "passive"))
    )
    (net (code "47") (name "DOUTB_ADC_2") (class "Default")
      (node (ref "J7") (pin "27") (pinfunction "27_27") (pintype "passive"))
    )
    (net (code "48") (name "DOUTB_ADC_3") (class "Default")
      (node (ref "J7") (pin "35") (pinfunction "35_35") (pintype "passive"))
    )
    (net (code "49") (name "D_SENSE1") (class "Default")
      (node (ref "J7") (pin "26") (pinfunction "26_26") (pintype "passive"))
    )
    (net (code "50") (name "D_SENSE2") (class "Default")
      (node (ref "J7") (pin "28") (pinfunction "28_28") (pintype "passive"))
    )
    (net (code "51") (name "D_SENSE3") (class "Default")
      (node (ref "J7") (pin "30") (pinfunction "30_30") (pintype "passive"))
    )
    (net (code "52") (name "D_SENSE4") (class "Default")
      (node (ref "J7") (pin "32") (pinfunction "32_32") (pintype "passive"))
    )
    (net (code "53") (name "D_SENSE5") (class "Default")
      (node (ref "J7") (pin "34") (pinfunction "34_34") (pintype "passive"))
    )
    (net (code "54") (name "D_SENSE6") (class "Default")
      (node (ref "J7") (pin "36") (pinfunction "36_36") (pintype "passive"))
    )
    (net (code "55") (name "D_SENSE7") (class "Default")
      (node (ref "J7") (pin "38") (pinfunction "38_38") (pintype "passive"))
    )
    (net (code "56") (name "D_SENSE8") (class "Default")
      (node (ref "J7") (pin "40") (pinfunction "40_40") (pintype "passive"))
    )
    (net (code "57") (name "ETH_CRS_DV") (class "Default")
      (node (ref "UC1") (pin "PA7") (pinfunction "PA7_PA7") (pintype "passive"))
    )
    (net (code "58") (name "ETH_MDC") (class "Default")
      (node (ref "UC1") (pin "PC1") (pinfunction "PC1_PC1") (pintype "passive"))
    )
    (net (code "59") (name "ETH_MDIO") (class "Default")
      (node (ref "UC1") (pin "PA2") (pinfunction "PA2_PA2") (pintype "passive"))
    )
    (net (code "60") (name "ETH_REF_CLK") (class "Default")
      (node (ref "UC1") (pin "PA1") (pinfunction "PA1_PA1") (pintype "passive"))
    )
    (net (code "61") (name "ETH_RXD0") (class "Default")
      (node (ref "UC1") (pin "PC4") (pinfunction "PC4_PC4") (pintype "passive"))
    )
    (net (code "62") (name "ETH_RXD1") (class "Default")
      (node (ref "UC1") (pin "PC5") (pinfunction "PC5_PC5") (pintype "passive"))
    )
    (net (code "63") (name "ETH_TXD0") (class "Default")
      (node (ref "UC1") (pin "PG13") (pinfunction "PG13_PG13") (pintype "passive"))
    )
    (net (code "64") (name "ETH_TXD1") (class "Default")
      (node (ref "UC1") (pin "PB13") (pinfunction "PB13_PB13") (pintype "passive"))
    )
    (net (code "65") (name "ETH_TX_EN") (class "Default")
      (node (ref "UC1") (pin "PG11") (pinfunction "PG11_PG11") (pintype "passive"))
    )
    (net (code "66") (name "FIRSTDATA_ADC_1") (class "Default")
      (node (ref "J7") (pin "17") (pinfunction "17_17") (pintype "passive"))
    )
    (net (code "67") (name "FIRSTDATA_ADC_2") (class "Default")
      (node (ref "J7") (pin "25") (pinfunction "25_25") (pintype "passive"))
    )
    (net (code "68") (name "FIRSTDATA_ADC_3") (class "Default")
      (node (ref "J7") (pin "33") (pinfunction "33_33") (pintype "passive"))
    )
    (net (code "69") (name "FIX_NC") (class "Default")
      (node (ref "J9") (pin "06") (pinfunction "06_06") (pintype "passive"))
    )
    (net (code "70") (name "GND") (class "Default")
      (node (ref "J2") (pin "2") (pinfunction "2_2") (pintype "passive"))
      (node (ref "J2") (pin "4") (pinfunction "4_4") (pintype "passive"))
      (node (ref "J2") (pin "6") (pinfunction "6_6") (pintype "passive"))
      (node (ref "J6") (pin "02") (pinfunction "02_02") (pintype "passive"))
      (node (ref "J6") (pin "04") (pinfunction "04_04") (pintype "passive"))
      (node (ref "J6") (pin "06") (pinfunction "06_06") (pintype "passive"))
      (node (ref "J6") (pin "08") (pinfunction "08_08") (pintype "passive"))
      (node (ref "J6") (pin "22") (pinfunction "22_22") (pintype "passive"))
      (node (ref "J6") (pin "24") (pinfunction "24_24") (pintype "passive"))
      (node (ref "J6") (pin "34") (pinfunction "34_34") (pintype "passive"))
      (node (ref "J6") (pin "36") (pinfunction "36_36") (pintype "passive"))
      (node (ref "J6") (pin "38") (pinfunction "38_38") (pintype "passive"))
      (node (ref "J6") (pin "39") (pinfunction "39_39") (pintype "passive"))
      (node (ref "J6") (pin "40") (pinfunction "40_40") (pintype "passive"))
      (node (ref "J9") (pin "03") (pinfunction "03_03") (pintype "passive"))
      (node (ref "UC1") (pin "10") (pinfunction "GND_10") (pintype "passive"))
      (node (ref "UC1") (pin "122") (pinfunction "GND_122") (pintype "passive"))
      (node (ref "UC1") (pin "131") (pinfunction "GND_131") (pintype "passive"))
      (node (ref "UC1") (pin "143") (pinfunction "GND_143") (pintype "passive"))
      (node (ref "UC1") (pin "144") (pinfunction "GND_144") (pintype "passive"))
      (node (ref "UC1") (pin "19") (pinfunction "GND_19") (pintype "passive"))
      (node (ref "UC1") (pin "40") (pinfunction "GND_40") (pintype "passive"))
      (node (ref "UC1") (pin "53") (pinfunction "GND_53") (pintype "passive"))
      (node (ref "UC1") (pin "64") (pinfunction "GND_64") (pintype "passive"))
      (node (ref "UC1") (pin "71") (pinfunction "GND_71") (pintype "passive"))
      (node (ref "UC1") (pin "72") (pinfunction "GND_72") (pintype "passive"))
      (node (ref "UC1") (pin "79") (pinfunction "GND_79") (pintype "passive"))
      (node (ref "UC1") (pin "91") (pinfunction "GND_91") (pintype "passive"))
      (node (ref "UC1") (pin "92") (pinfunction "GND_92") (pintype "passive"))
      (node (ref "UC1") (pin "93") (pinfunction "GND_93") (pintype "passive"))
      (node (ref "Z1") (pin "1") (pinfunction "GND_1") (pintype "bidirectional"))
      (node (ref "Z10") (pin "1") (pinfunction "GND_1") (pintype "bidirectional"))
      (node (ref "Z11") (pin "1") (pinfunction "GND_1") (pintype "bidirectional"))
      (node (ref "Z12") (pin "1") (pinfunction "GND_1") (pintype "bidirectional"))
      (node (ref "Z13") (pin "1") (pinfunction "GND_1") (pintype "bidirectional"))
      (node (ref "Z14") (pin "1") (pinfunction "GND_1") (pintype "bidirectional"))
      (node (ref "Z15") (pin "1") (pinfunction "GND_1") (pintype "bidirectional"))
      (node (ref "Z16") (pin "1") (pinfunction "GND_1") (pintype "bidirectional"))
      (node (ref "Z17") (pin "1") (pinfunction "GND_1") (pintype "bidirectional"))
      (node (ref "Z18") (pin "1") (pinfunction "GND_1") (pintype "bidirectional"))
      (node (ref "Z19") (pin "1") (pinfunction "GND_1") (pintype "bidirectional"))
      (node (ref "Z2") (pin "1") (pinfunction "GND_1") (pintype "bidirectional"))
      (node (ref "Z20") (pin "1") (pinfunction "GND_1") (pintype "bidirectional"))
      (node (ref "Z21") (pin "1") (pinfunction "GND_1") (pintype "bidirectional"))
      (node (ref "Z22") (pin "1") (pinfunction "GND_1") (pintype "bidirectional"))
      (node (ref "Z23") (pin "1") (pinfunction "GND_1") (pintype "bidirectional"))
      (node (ref "Z24") (pin "1") (pinfunction "GND_1") (pintype "bidirectional"))
      (node (ref "Z25") (pin "1") (pinfunction "GND_1") (pintype "bidirectional"))
      (node (ref "Z26") (pin "1") (pinfunction "GND_1") (pintype "bidirectional"))
      (node (ref "Z27") (pin "1") (pinfunction "GND_1") (pintype "bidirectional"))
      (node (ref "Z28") (pin "1") (pinfunction "GND_1") (pintype "bidirectional"))
      (node (ref "Z3") (pin "1") (pinfunction "GND_1") (pintype "bidirectional"))
      (node (ref "Z4") (pin "1") (pinfunction "GND_1") (pintype "bidirectional"))
      (node (ref "Z5") (pin "1") (pinfunction "GND_1") (pintype "bidirectional"))
      (node (ref "Z6") (pin "1") (pinfunction "GND_1") (pintype "bidirectional"))
      (node (ref "Z7") (pin "1") (pinfunction "GND_1") (pintype "bidirectional"))
      (node (ref "Z8") (pin "1") (pinfunction "GND_1") (pintype "bidirectional"))
      (node (ref "Z9") (pin "1") (pinfunction "GND_1") (pintype "bidirectional"))
    )
    (net (code "71") (name "GPS_EN") (class "Default")
      (node (ref "J8") (pin "39") (pinfunction "39_39") (pintype "passive"))
      (node (ref "J9") (pin "08") (pinfunction "08_08") (pintype "passive"))
    )
    (net (code "72") (name "GPS_RX") (class "Default")
      (node (ref "J8") (pin "37") (pinfunction "37_37") (pintype "passive"))
      (node (ref "J9") (pin "04") (pinfunction "04_04") (pintype "passive"))
    )
    (net (code "73") (name "GPS_TX") (class "Default")
      (node (ref "J8") (pin "35") (pinfunction "35_35") (pintype "passive"))
      (node (ref "J9") (pin "05") (pinfunction "05_05") (pintype "passive"))
    )
    (net (code "74") (name "IMU_DIN") (class "Default")
      (node (ref "J8") (pin "05") (pinfunction "05_05") (pintype "passive"))
    )
    (net (code "75") (name "IMU_DOUT") (class "Default")
      (node (ref "J8") (pin "07") (pinfunction "07_07") (pintype "passive"))
    )
    (net (code "76") (name "IMU_DR") (class "Default")
      (node (ref "J8") (pin "13") (pinfunction "13_13") (pintype "passive"))
    )
    (net (code "77") (name "IMU_SCLK") (class "Default")
      (node (ref "J8") (pin "09") (pinfunction "09_09") (pintype "passive"))
    )
    (net (code "78") (name "IMU_SYNC") (class "Default")
      (node (ref "J8") (pin "11") (pinfunction "11_11") (pintype "passive"))
    )
    (net (code "79") (name "IP_OUT1") (class "Default")
      (node (ref "Z15") (pin "5") (pinfunction "4_5") (pintype "bidirectional"))
    )
    (net (code "80") (name "ISO_MISO") (class "Default")
      (node (ref "J8") (pin "26") (pinfunction "26_26") (pintype "passive"))
    )
    (net (code "81") (name "ISO_MOSI") (class "Default")
      (node (ref "J8") (pin "24") (pinfunction "24_24") (pintype "passive"))
    )
    (net (code "82") (name "ISO_SPI_SCLK") (class "Default")
      (node (ref "J8") (pin "22") (pinfunction "22_22") (pintype "passive"))
    )
    (net (code "83") (name "ISO_SPI_SLOW") (class "Default")
      (node (ref "J8") (pin "30") (pinfunction "30_30") (pintype "passive"))
    )
    (net (code "84") (name "LED_OUT1") (class "Default")
      (node (ref "J7") (pin "22") (pinfunction "22_22") (pintype "passive"))
    )
    (net (code "85") (name "LED_OUT2") (class "Default")
      (node (ref "J7") (pin "20") (pinfunction "20_20") (pintype "passive"))
    )
    (net (code "86") (name "LED_OUT3") (class "Default")
      (node (ref "J7") (pin "18") (pinfunction "18_18") (pintype "passive"))
    )
    (net (code "87") (name "MASS_ON") (class "Default")
      (node (ref "J8") (pin "25") (pinfunction "25_25") (pintype "passive"))
    )
    (net (code "88") (name "MUX_0") (class "Default")
      (node (ref "J8") (pin "02") (pinfunction "02_02") (pintype "passive"))
    )
    (net (code "89") (name "MUX_1") (class "Default")
      (node (ref "J8") (pin "04") (pinfunction "04_04") (pintype "passive"))
    )
    (net (code "90") (name "MUX_2") (class "Default")
      (node (ref "J8") (pin "06") (pinfunction "06_06") (pintype "passive"))
    )
    (net (code "91") (name "MUX_3") (class "Default")
      (node (ref "J8") (pin "08") (pinfunction "08_08") (pintype "passive"))
    )
    (net (code "92") (name "NAND_SPI_CLK") (class "Default")
      (node (ref "J8") (pin "12") (pinfunction "12_12") (pintype "passive"))
    )
    (net (code "93") (name "NAND_SPI_SI{slash}IO0") (class "Default")
      (node (ref "J8") (pin "14") (pinfunction "14_14") (pintype "passive"))
    )
    (net (code "94") (name "NAND_SPI_SO{slash}IO1") (class "Default")
      (node (ref "J8") (pin "16") (pinfunction "16_16") (pintype "passive"))
    )
    (net (code "95") (name "NAND_SPI_~{HOLD{slash}IO03}") (class "Default")
      (node (ref "J8") (pin "20") (pinfunction "20_20") (pintype "passive"))
    )
    (net (code "96") (name "NAND_SPI_~{WP{slash}IO2}") (class "Default")
      (node (ref "J8") (pin "18") (pinfunction "18_18") (pintype "passive"))
    )
    (net (code "97") (name "OS0_ADC") (class "Default")
      (node (ref "J7") (pin "01") (pinfunction "01_01") (pintype "passive"))
    )
    (net (code "98") (name "OS1_ADC") (class "Default")
      (node (ref "J7") (pin "03") (pinfunction "03_03") (pintype "passive"))
    )
    (net (code "99") (name "OS2_ADC") (class "Default")
      (node (ref "J7") (pin "05") (pinfunction "05_05") (pintype "passive"))
    )
    (net (code "100") (name "PA0") (class "Default")
      (node (ref "J4") (pin "01") (pinfunction "01_01") (pintype "passive"))
      (node (ref "UC1") (pin "PA0") (pinfunction "PA0_PA0") (pintype "passive"))
    )
    (net (code "101") (name "PA3") (class "Default")
      (node (ref "J4") (pin "03") (pinfunction "03_03") (pintype "passive"))
      (node (ref "UC1") (pin "PA3") (pinfunction "PA3_PA3") (pintype "passive"))
    )
    (net (code "102") (name "PA4") (class "Default")
      (node (ref "J4") (pin "05") (pinfunction "05_05") (pintype "passive"))
      (node (ref "UC1") (pin "PA4") (pinfunction "PA4_PA4") (pintype "passive"))
    )
    (net (code "103") (name "PA5") (class "Default")
      (node (ref "J4") (pin "07") (pinfunction "07_07") (pintype "passive"))
      (node (ref "UC1") (pin "PA5") (pinfunction "PA5_PA5") (pintype "passive"))
    )
    (net (code "104") (name "PA6") (class "Default")
      (node (ref "J4") (pin "09") (pinfunction "09_09") (pintype "passive"))
      (node (ref "UC1") (pin "PA6") (pinfunction "PA6_PA6") (pintype "passive"))
    )
    (net (code "105") (name "PA8") (class "Default")
      (node (ref "J4") (pin "11") (pinfunction "11_11") (pintype "passive"))
      (node (ref "UC1") (pin "PA8") (pinfunction "PA8_PA8") (pintype "passive"))
    )
    (net (code "106") (name "PA9") (class "Default")
      (node (ref "J4") (pin "13") (pinfunction "13_13") (pintype "passive"))
      (node (ref "UC1") (pin "PA9") (pinfunction "PA9_PA9") (pintype "passive"))
    )
    (net (code "107") (name "PA10") (class "Default")
      (node (ref "J4") (pin "15") (pinfunction "15_15") (pintype "passive"))
      (node (ref "UC1") (pin "PA10") (pinfunction "PA10_PA10") (pintype "passive"))
    )
    (net (code "108") (name "PA11") (class "Default")
      (node (ref "J4") (pin "17") (pinfunction "17_17") (pintype "passive"))
      (node (ref "UC1") (pin "PA11") (pinfunction "PA11_PA11") (pintype "passive"))
    )
    (net (code "109") (name "PA12") (class "Default")
      (node (ref "J4") (pin "19") (pinfunction "19_19") (pintype "passive"))
      (node (ref "UC1") (pin "PA12") (pinfunction "PA12_PA12") (pintype "passive"))
    )
    (net (code "110") (name "PA13") (class "Default")
      (node (ref "J4") (pin "21") (pinfunction "21_21") (pintype "passive"))
      (node (ref "UC1") (pin "PA13") (pinfunction "PA13_PA13") (pintype "passive"))
    )
    (net (code "111") (name "PA14") (class "Default")
      (node (ref "J4") (pin "23") (pinfunction "23_23") (pintype "passive"))
      (node (ref "UC1") (pin "PA14") (pinfunction "PA14_PA14") (pintype "passive"))
    )
    (net (code "112") (name "PA15") (class "Default")
      (node (ref "J4") (pin "25") (pinfunction "25_25") (pintype "passive"))
      (node (ref "UC1") (pin "PA15") (pinfunction "PA15_PA15") (pintype "passive"))
    )
    (net (code "113") (name "PB0") (class "Default")
      (node (ref "J4") (pin "27") (pinfunction "27_27") (pintype "passive"))
      (node (ref "UC1") (pin "PB0") (pinfunction "PB0_PB0") (pintype "passive"))
    )
    (net (code "114") (name "PB1") (class "Default")
      (node (ref "J4") (pin "29") (pinfunction "29_29") (pintype "passive"))
      (node (ref "UC1") (pin "PB1") (pinfunction "PB1_PB1") (pintype "passive"))
    )
    (net (code "115") (name "PB2") (class "Default")
      (node (ref "J4") (pin "31") (pinfunction "31_31") (pintype "passive"))
      (node (ref "UC1") (pin "PB2") (pinfunction "PB2_PB2") (pintype "passive"))
    )
    (net (code "116") (name "PB3") (class "Default")
      (node (ref "J4") (pin "33") (pinfunction "33_33") (pintype "passive"))
      (node (ref "UC1") (pin "PB3") (pinfunction "PB3_PB3") (pintype "passive"))
    )
    (net (code "117") (name "PB4") (class "Default")
      (node (ref "J4") (pin "35") (pinfunction "35_35") (pintype "passive"))
      (node (ref "UC1") (pin "PB4") (pinfunction "PB4_PB4") (pintype "passive"))
    )
    (net (code "118") (name "PB5") (class "Default")
      (node (ref "J4") (pin "37") (pinfunction "37_37") (pintype "passive"))
      (node (ref "UC1") (pin "PB5") (pinfunction "PB5_PB5") (pintype "passive"))
    )
    (net (code "119") (name "PB6") (class "Default")
      (node (ref "J4") (pin "39") (pinfunction "39_39") (pintype "passive"))
      (node (ref "UC1") (pin "PB6") (pinfunction "PB6_PB6") (pintype "passive"))
    )
    (net (code "120") (name "PB7") (class "Default")
      (node (ref "J4") (pin "40") (pinfunction "40_40") (pintype "passive"))
      (node (ref "UC1") (pin "PB7") (pinfunction "PB7_PB7") (pintype "passive"))
    )
    (net (code "121") (name "PB8") (class "Default")
      (node (ref "J4") (pin "38") (pinfunction "38_38") (pintype "passive"))
      (node (ref "UC1") (pin "PB8") (pinfunction "PB8_PB8") (pintype "passive"))
    )
    (net (code "122") (name "PB9") (class "Default")
      (node (ref "J4") (pin "36") (pinfunction "36_36") (pintype "passive"))
      (node (ref "UC1") (pin "PB9") (pinfunction "PB9_PB9") (pintype "passive"))
    )
    (net (code "123") (name "PB10") (class "Default")
      (node (ref "J4") (pin "34") (pinfunction "34_34") (pintype "passive"))
      (node (ref "UC1") (pin "PB10") (pinfunction "PB10_PB10") (pintype "passive"))
    )
    (net (code "124") (name "PB11") (class "Default")
      (node (ref "J4") (pin "32") (pinfunction "32_32") (pintype "passive"))
      (node (ref "UC1") (pin "PB11") (pinfunction "PB11_PB11") (pintype "passive"))
    )
    (net (code "125") (name "PB12") (class "Default")
      (node (ref "J4") (pin "30") (pinfunction "30_30") (pintype "passive"))
      (node (ref "UC1") (pin "PB12") (pinfunction "PB12_PB12") (pintype "passive"))
    )
    (net (code "126") (name "PB13") (class "Default")
      (node (ref "J4") (pin "28") (pinfunction "28_28") (pintype "passive"))
    )
    (net (code "127") (name "PB14") (class "Default")
      (node (ref "J4") (pin "26") (pinfunction "26_26") (pintype "passive"))
      (node (ref "UC1") (pin "PB14") (pinfunction "PB14_PB14") (pintype "passive"))
    )
    (net (code "128") (name "PB15") (class "Default")
      (node (ref "J4") (pin "24") (pinfunction "24_24") (pintype "passive"))
      (node (ref "UC1") (pin "PB15") (pinfunction "PB15_PB15") (pintype "passive"))
    )
    (net (code "129") (name "PC0") (class "Default")
      (node (ref "J4") (pin "22") (pinfunction "22_22") (pintype "passive"))
      (node (ref "UC1") (pin "PC0") (pinfunction "PC0_PC0") (pintype "passive"))
    )
    (net (code "130") (name "PC2") (class "Default")
      (node (ref "J4") (pin "20") (pinfunction "20_20") (pintype "passive"))
      (node (ref "UC1") (pin "PC2") (pinfunction "PC2_PC2") (pintype "passive"))
    )
    (net (code "131") (name "PC3") (class "Default")
      (node (ref "J4") (pin "18") (pinfunction "18_18") (pintype "passive"))
      (node (ref "UC1") (pin "PC3") (pinfunction "PC3_PC3") (pintype "passive"))
    )
    (net (code "132") (name "PC6") (class "Default")
      (node (ref "J4") (pin "16") (pinfunction "16_16") (pintype "passive"))
      (node (ref "UC1") (pin "PC6") (pinfunction "PC6_PC6") (pintype "passive"))
    )
    (net (code "133") (name "PC7") (class "Default")
      (node (ref "J4") (pin "14") (pinfunction "14_14") (pintype "passive"))
      (node (ref "UC1") (pin "PC7") (pinfunction "PC7_PC7") (pintype "passive"))
    )
    (net (code "134") (name "PC8") (class "Default")
      (node (ref "J4") (pin "12") (pinfunction "12_12") (pintype "passive"))
      (node (ref "UC1") (pin "PC8") (pinfunction "PC8_PC8") (pintype "passive"))
    )
    (net (code "135") (name "PC9") (class "Default")
      (node (ref "J4") (pin "10") (pinfunction "10_10") (pintype "passive"))
      (node (ref "UC1") (pin "PC9") (pinfunction "PC9_PC9") (pintype "passive"))
    )
    (net (code "136") (name "PC10") (class "Default")
      (node (ref "J4") (pin "08") (pinfunction "08_08") (pintype "passive"))
      (node (ref "UC1") (pin "PC10") (pinfunction "PC10_PC10") (pintype "passive"))
    )
    (net (code "137") (name "PC11") (class "Default")
      (node (ref "J4") (pin "06") (pinfunction "06_06") (pintype "passive"))
      (node (ref "UC1") (pin "PC11") (pinfunction "PC11_PC11") (pintype "passive"))
    )
    (net (code "138") (name "PC12") (class "Default")
      (node (ref "J4") (pin "04") (pinfunction "04_04") (pintype "passive"))
      (node (ref "UC1") (pin "PC12") (pinfunction "PC12_PC12") (pintype "passive"))
    )
    (net (code "139") (name "PC13") (class "Default")
      (node (ref "J4") (pin "02") (pinfunction "02_02") (pintype "passive"))
      (node (ref "UC1") (pin "PC13") (pinfunction "PC13_PC13") (pintype "passive"))
    )
    (net (code "140") (name "PC14-0SC32_IN") (class "Default")
      (node (ref "UC1") (pin "PC14") (pinfunction "PC14_PC14") (pintype "passive"))
    )
    (net (code "141") (name "PC15-OSC32_OUT") (class "Default")
      (node (ref "UC1") (pin "PC15") (pinfunction "PC15_PC15") (pintype "passive"))
    )
    (net (code "142") (name "PD0") (class "Default")
      (node (ref "J5") (pin "01") (pinfunction "01_01") (pintype "passive"))
      (node (ref "UC1") (pin "PD0") (pinfunction "PD0_PD0") (pintype "passive"))
    )
    (net (code "143") (name "PD1") (class "Default")
      (node (ref "J5") (pin "03") (pinfunction "03_03") (pintype "passive"))
      (node (ref "UC1") (pin "PD1") (pinfunction "PD1_PD1") (pintype "passive"))
    )
    (net (code "144") (name "PD2") (class "Default")
      (node (ref "J5") (pin "05") (pinfunction "05_05") (pintype "passive"))
      (node (ref "UC1") (pin "PD2") (pinfunction "PD2_PD2") (pintype "passive"))
    )
    (net (code "145") (name "PD3") (class "Default")
      (node (ref "J5") (pin "07") (pinfunction "07_07") (pintype "passive"))
      (node (ref "UC1") (pin "PD3") (pinfunction "PD3_PD3") (pintype "passive"))
    )
    (net (code "146") (name "PD4") (class "Default")
      (node (ref "J5") (pin "09") (pinfunction "09_09") (pintype "passive"))
      (node (ref "UC1") (pin "PD4") (pinfunction "PD4_PD4") (pintype "passive"))
    )
    (net (code "147") (name "PD5") (class "Default")
      (node (ref "J5") (pin "11") (pinfunction "11_11") (pintype "passive"))
      (node (ref "UC1") (pin "PD5") (pinfunction "PD5_PD5") (pintype "passive"))
    )
    (net (code "148") (name "PD6") (class "Default")
      (node (ref "J5") (pin "13") (pinfunction "13_13") (pintype "passive"))
      (node (ref "UC1") (pin "PD6") (pinfunction "PD6_PD6") (pintype "passive"))
    )
    (net (code "149") (name "PD7") (class "Default")
      (node (ref "J5") (pin "15") (pinfunction "15_15") (pintype "passive"))
      (node (ref "UC1") (pin "PD7") (pinfunction "PD7_PD7") (pintype "passive"))
    )
    (net (code "150") (name "PD11") (class "Default")
      (node (ref "J5") (pin "17") (pinfunction "17_17") (pintype "passive"))
      (node (ref "UC1") (pin "PD11") (pinfunction "PD11_PD11") (pintype "passive"))
    )
    (net (code "151") (name "PD12") (class "Default")
      (node (ref "J5") (pin "19") (pinfunction "19_19") (pintype "passive"))
      (node (ref "UC1") (pin "PD12") (pinfunction "PD12_PD12") (pintype "passive"))
    )
    (net (code "152") (name "PD13") (class "Default")
      (node (ref "J5") (pin "21") (pinfunction "21_21") (pintype "passive"))
      (node (ref "UC1") (pin "PD13") (pinfunction "PD13_PD13") (pintype "passive"))
    )
    (net (code "153") (name "PD14") (class "Default")
      (node (ref "J5") (pin "23") (pinfunction "23_23") (pintype "passive"))
      (node (ref "UC1") (pin "PD14") (pinfunction "PD14_PD14") (pintype "passive"))
    )
    (net (code "154") (name "PD15") (class "Default")
      (node (ref "J5") (pin "25") (pinfunction "25_25") (pintype "passive"))
      (node (ref "UC1") (pin "PD15") (pinfunction "PD15_PD15") (pintype "passive"))
    )
    (net (code "155") (name "PE0") (class "Default")
      (node (ref "J5") (pin "27") (pinfunction "27_27") (pintype "passive"))
      (node (ref "UC1") (pin "PE0") (pinfunction "PE0_PE0") (pintype "passive"))
    )
    (net (code "156") (name "PE1") (class "Default")
      (node (ref "J5") (pin "29") (pinfunction "29_29") (pintype "passive"))
      (node (ref "UC1") (pin "PE1") (pinfunction "PE1_PE1") (pintype "passive"))
    )
    (net (code "157") (name "PE2") (class "Default")
      (node (ref "J5") (pin "31") (pinfunction "31_31") (pintype "passive"))
      (node (ref "UC1") (pin "PE2") (pinfunction "PE2_PE2") (pintype "passive"))
    )
    (net (code "158") (name "PE3") (class "Default")
      (node (ref "J5") (pin "33") (pinfunction "33_33") (pintype "passive"))
      (node (ref "UC1") (pin "PE3") (pinfunction "PE3_PE3") (pintype "passive"))
    )
    (net (code "159") (name "PE4") (class "Default")
      (node (ref "J5") (pin "35") (pinfunction "35_35") (pintype "passive"))
      (node (ref "UC1") (pin "PE4") (pinfunction "PE4_PE4") (pintype "passive"))
    )
    (net (code "160") (name "PE5") (class "Default")
      (node (ref "J5") (pin "37") (pinfunction "37_37") (pintype "passive"))
      (node (ref "UC1") (pin "PE5") (pinfunction "PE5_PE5") (pintype "passive"))
    )
    (net (code "161") (name "PE6") (class "Default")
      (node (ref "J5") (pin "39") (pinfunction "39_39") (pintype "passive"))
      (node (ref "UC1") (pin "PE6") (pinfunction "PE6_PE6") (pintype "passive"))
    )
    (net (code "162") (name "PE7") (class "Default")
      (node (ref "J5") (pin "40") (pinfunction "40_40") (pintype "passive"))
      (node (ref "UC1") (pin "PE7") (pinfunction "PE7_PE7") (pintype "passive"))
    )
    (net (code "163") (name "PE8") (class "Default")
      (node (ref "J5") (pin "38") (pinfunction "38_38") (pintype "passive"))
      (node (ref "UC1") (pin "PE8") (pinfunction "PE8_PE8") (pintype "passive"))
    )
    (net (code "164") (name "PE9") (class "Default")
      (node (ref "J5") (pin "36") (pinfunction "36_36") (pintype "passive"))
      (node (ref "UC1") (pin "PE9") (pinfunction "PE9_PE9") (pintype "passive"))
    )
    (net (code "165") (name "PE10") (class "Default")
      (node (ref "J5") (pin "34") (pinfunction "34_34") (pintype "passive"))
      (node (ref "UC1") (pin "PE10") (pinfunction "PE10_PE10") (pintype "passive"))
    )
    (net (code "166") (name "PE11") (class "Default")
      (node (ref "J5") (pin "32") (pinfunction "32_32") (pintype "passive"))
      (node (ref "UC1") (pin "PE11") (pinfunction "PE11_PE11") (pintype "passive"))
    )
    (net (code "167") (name "PE12") (class "Default")
      (node (ref "J5") (pin "30") (pinfunction "30_30") (pintype "passive"))
      (node (ref "UC1") (pin "PE12") (pinfunction "PE12_PE12") (pintype "passive"))
    )
    (net (code "168") (name "PE13") (class "Default")
      (node (ref "J5") (pin "28") (pinfunction "28_28") (pintype "passive"))
      (node (ref "UC1") (pin "PE13") (pinfunction "PE13_PE13") (pintype "passive"))
    )
    (net (code "169") (name "PE14") (class "Default")
      (node (ref "J5") (pin "26") (pinfunction "26_26") (pintype "passive"))
      (node (ref "UC1") (pin "PE14") (pinfunction "PE14_PE14") (pintype "passive"))
    )
    (net (code "170") (name "PE15") (class "Default")
      (node (ref "J5") (pin "24") (pinfunction "24_24") (pintype "passive"))
      (node (ref "UC1") (pin "PE15") (pinfunction "PE15_PE15") (pintype "passive"))
    )
    (net (code "171") (name "PF0") (class "Default")
      (node (ref "UC1") (pin "PF0") (pinfunction "PF0_PF0") (pintype "passive"))
    )
    (net (code "172") (name "PF1") (class "Default")
      (node (ref "J5") (pin "22") (pinfunction "22_22") (pintype "passive"))
      (node (ref "UC1") (pin "PF1") (pinfunction "PF1_PF1") (pintype "passive"))
    )
    (net (code "173") (name "PF2") (class "Default")
      (node (ref "J5") (pin "20") (pinfunction "20_20") (pintype "passive"))
      (node (ref "UC1") (pin "PF2") (pinfunction "PF2_PF2") (pintype "passive"))
    )
    (net (code "174") (name "PF3") (class "Default")
      (node (ref "J5") (pin "18") (pinfunction "18_18") (pintype "passive"))
      (node (ref "UC1") (pin "PF3") (pinfunction "PF3_PF3") (pintype "passive"))
    )
    (net (code "175") (name "PF4") (class "Default")
      (node (ref "J5") (pin "16") (pinfunction "16_16") (pintype "passive"))
      (node (ref "UC1") (pin "PF4") (pinfunction "PF4_PF4") (pintype "passive"))
    )
    (net (code "176") (name "PF5") (class "Default")
      (node (ref "J5") (pin "14") (pinfunction "14_14") (pintype "passive"))
      (node (ref "UC1") (pin "PF5") (pinfunction "PF5_PF5") (pintype "passive"))
    )
    (net (code "177") (name "PF6") (class "Default")
      (node (ref "J5") (pin "12") (pinfunction "12_12") (pintype "passive"))
      (node (ref "UC1") (pin "PF6") (pinfunction "PF6_PF6") (pintype "passive"))
    )
    (net (code "178") (name "PF7") (class "Default")
      (node (ref "J5") (pin "10") (pinfunction "10_10") (pintype "passive"))
      (node (ref "UC1") (pin "PF7") (pinfunction "PF7_PF7") (pintype "passive"))
    )
    (net (code "179") (name "PF8") (class "Default")
      (node (ref "J5") (pin "08") (pinfunction "08_08") (pintype "passive"))
      (node (ref "UC1") (pin "PF8") (pinfunction "PF8_PF8") (pintype "passive"))
    )
    (net (code "180") (name "PF9") (class "Default")
      (node (ref "J5") (pin "06") (pinfunction "06_06") (pintype "passive"))
      (node (ref "UC1") (pin "PF9") (pinfunction "PF9_PF9") (pintype "passive"))
    )
    (net (code "181") (name "PF10") (class "Default")
      (node (ref "J5") (pin "04") (pinfunction "04_04") (pintype "passive"))
      (node (ref "UC1") (pin "PF10") (pinfunction "PF10_PF10") (pintype "passive"))
    )
    (net (code "182") (name "PF11") (class "Default")
      (node (ref "J5") (pin "02") (pinfunction "02_02") (pintype "passive"))
      (node (ref "UC1") (pin "PF11") (pinfunction "PF11_PF11") (pintype "passive"))
    )
    (net (code "183") (name "PF12") (class "Default")
      (node (ref "J6") (pin "01") (pinfunction "01_01") (pintype "passive"))
      (node (ref "UC1") (pin "PF12") (pinfunction "PF12_PF12") (pintype "passive"))
    )
    (net (code "184") (name "PF13") (class "Default")
      (node (ref "J6") (pin "03") (pinfunction "03_03") (pintype "passive"))
      (node (ref "UC1") (pin "PF13") (pinfunction "PF13_PF13") (pintype "passive"))
    )
    (net (code "185") (name "PF14") (class "Default")
      (node (ref "J6") (pin "05") (pinfunction "05_05") (pintype "passive"))
      (node (ref "UC1") (pin "PF14") (pinfunction "PF14_PF14") (pintype "passive"))
    )
    (net (code "186") (name "PF15") (class "Default")
      (node (ref "J6") (pin "07") (pinfunction "07_07") (pintype "passive"))
      (node (ref "UC1") (pin "PF15") (pinfunction "PF15_PF15") (pintype "passive"))
    )
    (net (code "187") (name "PG0") (class "Default")
      (node (ref "J6") (pin "09") (pinfunction "09_09") (pintype "passive"))
      (node (ref "UC1") (pin "PG0") (pinfunction "PG0_PG0") (pintype "passive"))
    )
    (net (code "188") (name "PG1") (class "Default")
      (node (ref "J6") (pin "11") (pinfunction "11_11") (pintype "passive"))
      (node (ref "UC1") (pin "PG1") (pinfunction "PG1_PG1") (pintype "passive"))
    )
    (net (code "189") (name "PG2") (class "Default")
      (node (ref "J6") (pin "13") (pinfunction "13_13") (pintype "passive"))
      (node (ref "UC1") (pin "PG2") (pinfunction "PG2_PG2") (pintype "passive"))
    )
    (net (code "190") (name "PG3") (class "Default")
      (node (ref "J6") (pin "15") (pinfunction "15_15") (pintype "passive"))
      (node (ref "UC1") (pin "PG3") (pinfunction "PG3_PG3") (pintype "passive"))
    )
    (net (code "191") (name "PG4") (class "Default")
      (node (ref "J6") (pin "17") (pinfunction "17_17") (pintype "passive"))
      (node (ref "UC1") (pin "PG4") (pinfunction "PG4_PG4") (pintype "passive"))
    )
    (net (code "192") (name "PG5") (class "Default")
      (node (ref "J6") (pin "19") (pinfunction "19_19") (pintype "passive"))
      (node (ref "UC1") (pin "PG5") (pinfunction "PG5_PG5") (pintype "passive"))
    )
    (net (code "193") (name "PG6") (class "Default")
      (node (ref "J6") (pin "21") (pinfunction "21_21") (pintype "passive"))
      (node (ref "UC1") (pin "PG6") (pinfunction "PG6_PG6") (pintype "passive"))
    )
    (net (code "194") (name "PG7") (class "Default")
      (node (ref "J6") (pin "23") (pinfunction "23_23") (pintype "passive"))
    )
    (net (code "195") (name "PG8") (class "Default")
      (node (ref "J6") (pin "25") (pinfunction "25_25") (pintype "passive"))
      (node (ref "UC1") (pin "PG8") (pinfunction "PG8_PG8") (pintype "passive"))
    )
    (net (code "196") (name "PG9") (class "Default")
      (node (ref "J6") (pin "27") (pinfunction "27_27") (pintype "passive"))
      (node (ref "UC1") (pin "PG9") (pinfunction "PG9_PG9") (pintype "passive"))
    )
    (net (code "197") (name "PG10") (class "Default")
      (node (ref "J6") (pin "29") (pinfunction "29_29") (pintype "passive"))
      (node (ref "UC1") (pin "PG10") (pinfunction "PG10_PG10") (pintype "passive"))
    )
    (net (code "198") (name "PG12") (class "Default")
      (node (ref "J6") (pin "31") (pinfunction "31_31") (pintype "passive"))
      (node (ref "UC1") (pin "PG12") (pinfunction "PG12_PG12") (pintype "passive"))
    )
    (net (code "199") (name "PG14") (class "Default")
      (node (ref "J6") (pin "33") (pinfunction "33_33") (pintype "passive"))
      (node (ref "UC1") (pin "PG14") (pinfunction "PG14_PG14") (pintype "passive"))
    )
    (net (code "200") (name "PG15") (class "Default")
      (node (ref "J6") (pin "35") (pinfunction "35_35") (pintype "passive"))
      (node (ref "UC1") (pin "PG15") (pinfunction "PG15_PG15") (pintype "passive"))
    )
    (net (code "201") (name "PH0-OSC_IN") (class "Default")
      (node (ref "UC1") (pin "PH0") (pinfunction "PH0_PH0") (pintype "passive"))
    )
    (net (code "202") (name "PH1") (class "Default")
      (node (ref "J6") (pin "37") (pinfunction "37_37") (pintype "passive"))
      (node (ref "UC1") (pin "PH1") (pinfunction "PH1_PH1") (pintype "passive"))
    )
    (net (code "203") (name "POWER_FAULT1") (class "Default")
      (node (ref "J2") (pin "7") (pinfunction "7_7") (pintype "passive"))
      (node (ref "J8") (pin "15") (pinfunction "15_15") (pintype "passive"))
    )
    (net (code "204") (name "POWER_FAULT2") (class "Default")
      (node (ref "J2") (pin "9") (pinfunction "9_9") (pintype "passive"))
      (node (ref "J8") (pin "17") (pinfunction "17_17") (pintype "passive"))
    )
    (net (code "205") (name "POWER_FAULT3") (class "Default")
      (node (ref "J2") (pin "11") (pinfunction "11_11") (pintype "passive"))
      (node (ref "J8") (pin "19") (pinfunction "19_19") (pintype "passive"))
    )
    (net (code "206") (name "PPS_NC") (class "Default")
      (node (ref "J9") (pin "01") (pinfunction "01_01") (pintype "passive"))
    )
    (net (code "207") (name "P_LED") (class "Default")
      (node (ref "J7") (pin "24") (pinfunction "24_24") (pintype "passive"))
    )
    (net (code "208") (name "RESET_ADC") (class "Default")
      (node (ref "J7") (pin "09") (pinfunction "09_09") (pintype "passive"))
    )
    (net (code "209") (name "SCL1") (class "Default")
      (node (ref "J8") (pin "23") (pinfunction "23_23") (pintype "passive"))
    )
    (net (code "210") (name "SCL2") (class "Default")
      (node (ref "J8") (pin "29") (pinfunction "29_29") (pintype "passive"))
    )
    (net (code "211") (name "SCLK_ADC") (class "Default")
      (node (ref "J7") (pin "11") (pinfunction "11_11") (pintype "passive"))
    )
    (net (code "212") (name "SDA1") (class "Default")
      (node (ref "J8") (pin "21") (pinfunction "21_21") (pintype "passive"))
    )
    (net (code "213") (name "SDA2") (class "Default")
      (node (ref "J8") (pin "27") (pinfunction "27_27") (pintype "passive"))
    )
    (net (code "214") (name "SOURCE1_") (class "Default")
      (node (ref "Z1") (pin "2") (pinfunction "1_2") (pintype "bidirectional"))
    )
    (net (code "215") (name "SOURCE1_0") (class "Default")
      (node (ref "Z3") (pin "2") (pinfunction "1_2") (pintype "bidirectional"))
    )
    (net (code "216") (name "SOURCE1_1") (class "Default")
      (node (ref "Z21") (pin "2") (pinfunction "1_2") (pintype "bidirectional"))
    )
    (net (code "217") (name "SOURCE1_2") (class "Default")
      (node (ref "Z23") (pin "2") (pinfunction "1_2") (pintype "bidirectional"))
    )
    (net (code "218") (name "SOURCE1_3") (class "Default")
      (node (ref "Z5") (pin "2") (pinfunction "1_2") (pintype "bidirectional"))
    )
    (net (code "219") (name "SOURCE1_4") (class "Default")
      (node (ref "Z7") (pin "2") (pinfunction "1_2") (pintype "bidirectional"))
    )
    (net (code "220") (name "SOURCE1_5") (class "Default")
      (node (ref "Z17") (pin "2") (pinfunction "1_2") (pintype "bidirectional"))
    )
    (net (code "221") (name "SOURCE1_6") (class "Default")
      (node (ref "Z19") (pin "2") (pinfunction "1_2") (pintype "bidirectional"))
    )
    (net (code "222") (name "SOURCE1_7") (class "Default")
      (node (ref "Z9") (pin "2") (pinfunction "1_2") (pintype "bidirectional"))
    )
    (net (code "223") (name "SOURCE1_8") (class "Default")
      (node (ref "Z11") (pin "2") (pinfunction "1_2") (pintype "bidirectional"))
    )
    (net (code "224") (name "SOURCE1_9") (class "Default")
      (node (ref "Z13") (pin "2") (pinfunction "1_2") (pintype "bidirectional"))
    )
    (net (code "225") (name "SOURCE1_11") (class "Default")
      (node (ref "Z25") (pin "5") (pinfunction "4_5") (pintype "bidirectional"))
    )
    (net (code "226") (name "SOURCE1_12") (class "Default")
      (node (ref "Z26") (pin "5") (pinfunction "4_5") (pintype "bidirectional"))
    )
    (net (code "227") (name "SOURCE2_") (class "Default")
      (node (ref "Z2") (pin "2") (pinfunction "1_2") (pintype "bidirectional"))
    )
    (net (code "228") (name "SOURCE2_0") (class "Default")
      (node (ref "Z4") (pin "2") (pinfunction "1_2") (pintype "bidirectional"))
    )
    (net (code "229") (name "SOURCE2_1") (class "Default")
      (node (ref "Z22") (pin "2") (pinfunction "1_2") (pintype "bidirectional"))
    )
    (net (code "230") (name "SOURCE2_2") (class "Default")
      (node (ref "Z24") (pin "2") (pinfunction "1_2") (pintype "bidirectional"))
    )
    (net (code "231") (name "SOURCE2_3") (class "Default")
      (node (ref "Z6") (pin "2") (pinfunction "1_2") (pintype "bidirectional"))
    )
    (net (code "232") (name "SOURCE2_4") (class "Default")
      (node (ref "Z8") (pin "2") (pinfunction "1_2") (pintype "bidirectional"))
    )
    (net (code "233") (name "SOURCE2_5") (class "Default")
      (node (ref "Z18") (pin "2") (pinfunction "1_2") (pintype "bidirectional"))
    )
    (net (code "234") (name "SOURCE2_6") (class "Default")
      (node (ref "Z20") (pin "2") (pinfunction "1_2") (pintype "bidirectional"))
    )
    (net (code "235") (name "SOURCE2_7") (class "Default")
      (node (ref "Z10") (pin "2") (pinfunction "1_2") (pintype "bidirectional"))
    )
    (net (code "236") (name "SOURCE2_8") (class "Default")
      (node (ref "Z12") (pin "2") (pinfunction "1_2") (pintype "bidirectional"))
    )
    (net (code "237") (name "SOURCE2_9") (class "Default")
      (node (ref "Z14") (pin "2") (pinfunction "1_2") (pintype "bidirectional"))
    )
    (net (code "238") (name "SOURCE2_11") (class "Default")
      (node (ref "Z25") (pin "2") (pinfunction "1_2") (pintype "bidirectional"))
    )
    (net (code "239") (name "SOURCE2_12") (class "Default")
      (node (ref "Z26") (pin "2") (pinfunction "1_2") (pintype "bidirectional"))
    )
    (net (code "240") (name "THERMOCOUPLE_MISO") (class "Default")
      (node (ref "J8") (pin "34") (pinfunction "34_34") (pintype "passive"))
    )
    (net (code "241") (name "THERMOCOUPLE_SCLK") (class "Default")
      (node (ref "J8") (pin "32") (pinfunction "32_32") (pintype "passive"))
    )
    (net (code "242") (name "USART3_TX") (class "Default")
      (node (ref "UC1") (pin "PD8") (pinfunction "PD8_PD8") (pintype "passive"))
    )
    (net (code "243") (name "USART4_RX") (class "Default")
      (node (ref "UC1") (pin "PD9") (pinfunction "PD9_PD9") (pintype "passive"))
    )
    (net (code "244") (name "USB_FS_OVCR") (class "Default")
      (node (ref "UC1") (pin "PG7") (pinfunction "PG7_PG7") (pintype "passive"))
    )
    (net (code "245") (name "USB_FS_PWR_EN") (class "Default")
      (node (ref "UC1") (pin "PD10") (pinfunction "PD10_PD10") (pintype "passive"))
    )
    (net (code "246") (name "VBAT_NC") (class "Default")
      (node (ref "J9") (pin "07") (pinfunction "07_07") (pintype "passive"))
    )
    (net (code "247") (name "unconnected-(J1-Pad2)") (class "Default")
      (node (ref "J1") (pin "2") (pinfunction "2_2") (pintype "passive"))
    )
    (net (code "248") (name "unconnected-(J1-Pad4)") (class "Default")
      (node (ref "J1") (pin "4") (pinfunction "4_4") (pintype "passive"))
    )
    (net (code "249") (name "unconnected-(J1-Pad6)") (class "Default")
      (node (ref "J1") (pin "6") (pinfunction "6_6") (pintype "passive"))
    )
    (net (code "250") (name "unconnected-(J1-Pad8)") (class "Default")
      (node (ref "J1") (pin "8") (pinfunction "8_8") (pintype "passive"))
    )
    (net (code "251") (name "unconnected-(J7-Pad02)") (class "Default")
      (node (ref "J7") (pin "02") (pinfunction "02_02") (pintype "passive"))
    )
    (net (code "252") (name "unconnected-(J7-Pad04)") (class "Default")
      (node (ref "J7") (pin "04") (pinfunction "04_04") (pintype "passive"))
    )
    (net (code "253") (name "unconnected-(J7-Pad06)") (class "Default")
      (node (ref "J7") (pin "06") (pinfunction "06_06") (pintype "passive"))
    )
    (net (code "254") (name "unconnected-(J7-Pad08)") (class "Default")
      (node (ref "J7") (pin "08") (pinfunction "08_08") (pintype "passive"))
    )
    (net (code "255") (name "unconnected-(J7-Pad10)") (class "Default")
      (node (ref "J7") (pin "10") (pinfunction "10_10") (pintype "passive"))
    )
    (net (code "256") (name "unconnected-(J7-Pad12)") (class "Default")
      (node (ref "J7") (pin "12") (pinfunction "12_12") (pintype "passive"))
    )
    (net (code "257") (name "unconnected-(J7-Pad14)") (class "Default")
      (node (ref "J7") (pin "14") (pinfunction "14_14") (pintype "passive"))
    )
    (net (code "258") (name "unconnected-(J7-Pad16)") (class "Default")
      (node (ref "J7") (pin "16") (pinfunction "16_16") (pintype "passive"))
    )
    (net (code "259") (name "unconnected-(J7-Pad39)") (class "Default")
      (node (ref "J7") (pin "39") (pinfunction "39_39") (pintype "passive"))
    )
    (net (code "260") (name "unconnected-(J8-Pad31)") (class "Default")
      (node (ref "J8") (pin "31") (pinfunction "31_31") (pintype "passive"))
    )
    (net (code "261") (name "unconnected-(J8-Pad33)") (class "Default")
      (node (ref "J8") (pin "33") (pinfunction "33_33") (pintype "passive"))
    )
    (net (code "262") (name "unconnected-(J8-Pad38)") (class "Default")
      (node (ref "J8") (pin "38") (pinfunction "38_38") (pintype "passive"))
    )
    (net (code "263") (name "unconnected-(J8-Pad40)") (class "Default")
      (node (ref "J8") (pin "40") (pinfunction "40_40") (pintype "passive"))
    )
    (net (code "264") (name "unconnected-(U$1-THROUGH_HOLE-Pad1{slash}16IN)") (class "Default")
      (node (ref "U$1") (pin "1/16IN") (pinfunction "THROUGH_HOLE_1/16IN") (pintype "bidirectional"))
    )
    (net (code "265") (name "unconnected-(U$2-THROUGH_HOLE-Pad1{slash}16IN)") (class "Default")
      (node (ref "U$2") (pin "1/16IN") (pinfunction "THROUGH_HOLE_1/16IN") (pintype "bidirectional"))
    )
    (net (code "266") (name "unconnected-(U$3-THROUGH_HOLE-Pad1{slash}16IN)") (class "Default")
      (node (ref "U$3") (pin "1/16IN") (pinfunction "THROUGH_HOLE_1/16IN") (pintype "bidirectional"))
    )
    (net (code "267") (name "unconnected-(U$4-THROUGH_HOLE-Pad1{slash}16IN)") (class "Default")
      (node (ref "U$4") (pin "1/16IN") (pinfunction "THROUGH_HOLE_1/16IN") (pintype "bidirectional"))
    )
    (net (code "268") (name "unconnected-(U$5-THROUGH_HOLE-Pad1{slash}16IN)") (class "Default")
      (node (ref "U$5") (pin "1/16IN") (pinfunction "THROUGH_HOLE_1/16IN") (pintype "bidirectional"))
    )
    (net (code "269") (name "unconnected-(U$6-THROUGH_HOLE-Pad1{slash}16IN)") (class "Default")
      (node (ref "U$6") (pin "1/16IN") (pinfunction "THROUGH_HOLE_1/16IN") (pintype "bidirectional"))
    )
    (net (code "270") (name "unconnected-(U$7-THROUGH_HOLE-Pad1{slash}16IN)") (class "Default")
      (node (ref "U$7") (pin "1/16IN") (pinfunction "THROUGH_HOLE_1/16IN") (pintype "bidirectional"))
    )
    (net (code "271") (name "unconnected-(U$8-THROUGH_HOLE-Pad1{slash}16IN)") (class "Default")
      (node (ref "U$8") (pin "1/16IN") (pinfunction "THROUGH_HOLE_1/16IN") (pintype "bidirectional"))
    )
    (net (code "272") (name "unconnected-(U$9-THROUGH_HOLE-Pad1{slash}16IN)") (class "Default")
      (node (ref "U$9") (pin "1/16IN") (pinfunction "THROUGH_HOLE_1/16IN") (pintype "bidirectional"))
    )
    (net (code "273") (name "unconnected-(U$10-THROUGH_HOLE-Pad1{slash}16IN)") (class "Default")
      (node (ref "U$10") (pin "1/16IN") (pinfunction "THROUGH_HOLE_1/16IN") (pintype "bidirectional"))
    )
    (net (code "274") (name "unconnected-(U$11-THROUGH_HOLE-Pad1{slash}16IN)") (class "Default")
      (node (ref "U$11") (pin "1/16IN") (pinfunction "THROUGH_HOLE_1/16IN") (pintype "bidirectional"))
    )
    (net (code "275") (name "unconnected-(U$12-THROUGH_HOLE-Pad1{slash}16IN)") (class "Default")
      (node (ref "U$12") (pin "1/16IN") (pinfunction "THROUGH_HOLE_1/16IN") (pintype "bidirectional"))
    )
    (net (code "276") (name "unconnected-(UC1-AGND-Pad31_AGND)") (class "Default")
      (node (ref "UC1") (pin "31_AGND") (pinfunction "AGND_31_AGND") (pintype "passive"))
    )
    (net (code "277") (name "unconnected-(UC1-Pad3V3)") (class "Default")
      (node (ref "UC1") (pin "3V3") (pinfunction "3V3_3V3") (pintype "passive"))
    )
    (net (code "278") (name "unconnected-(UC1-Pad5V)") (class "Default")
      (node (ref "UC1") (pin "5V") (pinfunction "5V_5V") (pintype "passive"))
    )
    (net (code "279") (name "unconnected-(UC1-Pad5V_USB_STLK)") (class "Default")
      (node (ref "UC1") (pin "5V_USB_STLK") (pinfunction "5V_USB_STLK_5V_USB_STLK") (pintype "passive"))
    )
    (net (code "280") (name "unconnected-(UC1-PadBOOT0)") (class "Default")
      (node (ref "UC1") (pin "BOOT0") (pinfunction "BOOT0_BOOT0") (pintype "passive"))
    )
    (net (code "281") (name "unconnected-(UC1-PadIOREF)") (class "Default")
      (node (ref "UC1") (pin "IOREF") (pinfunction "IOREF_IOREF") (pintype "passive"))
    )
    (net (code "282") (name "unconnected-(UC1-PadNC_1)") (class "Default")
      (node (ref "UC1") (pin "NC_1") (pinfunction "NC_1_NC_1") (pintype "passive"))
    )
    (net (code "283") (name "unconnected-(UC1-PadNC_2)") (class "Default")
      (node (ref "UC1") (pin "NC_2") (pinfunction "NC_2_NC_2") (pintype "passive"))
    )
    (net (code "284") (name "unconnected-(UC1-PadNC_3)") (class "Default")
      (node (ref "UC1") (pin "NC_3") (pinfunction "NC_3_NC_3") (pintype "passive"))
    )
    (net (code "285") (name "unconnected-(UC1-PadNRST)") (class "Default")
      (node (ref "UC1") (pin "NRST") (pinfunction "NRST_NRST") (pintype "passive"))
    )
    (net (code "286") (name "unconnected-(UC1-PadVBAT)") (class "Default")
      (node (ref "UC1") (pin "VBAT") (pinfunction "VBAT_VBAT") (pintype "passive"))
    )
    (net (code "287") (name "unconnected-(UC1-PadVIN)") (class "Default")
      (node (ref "UC1") (pin "VIN") (pinfunction "VIN_VIN") (pintype "passive"))
    )
    (net (code "288") (name "unconnected-(UC1-PadVREFP)") (class "Default")
      (node (ref "UC1") (pin "VREFP") (pinfunction "VREFP_VREFP") (pintype "passive"))
    )
    (net (code "289") (name "unconnected-(Z1-2-Pad3)") (class "Default")
      (node (ref "Z1") (pin "3") (pinfunction "2_3") (pintype "bidirectional"))
    )
    (net (code "290") (name "unconnected-(Z1-4-Pad5)") (class "Default")
      (node (ref "Z1") (pin "5") (pinfunction "4_5") (pintype "bidirectional"))
    )
    (net (code "291") (name "unconnected-(Z2-2-Pad3)") (class "Default")
      (node (ref "Z2") (pin "3") (pinfunction "2_3") (pintype "bidirectional"))
    )
    (net (code "292") (name "unconnected-(Z2-3-Pad4)") (class "Default")
      (node (ref "Z2") (pin "4") (pinfunction "3_4") (pintype "bidirectional"))
    )
    (net (code "293") (name "unconnected-(Z3-2-Pad3)") (class "Default")
      (node (ref "Z3") (pin "3") (pinfunction "2_3") (pintype "bidirectional"))
    )
    (net (code "294") (name "unconnected-(Z3-3-Pad4)") (class "Default")
      (node (ref "Z3") (pin "4") (pinfunction "3_4") (pintype "bidirectional"))
    )
    (net (code "295") (name "unconnected-(Z4-2-Pad3)") (class "Default")
      (node (ref "Z4") (pin "3") (pinfunction "2_3") (pintype "bidirectional"))
    )
    (net (code "296") (name "unconnected-(Z4-3-Pad4)") (class "Default")
      (node (ref "Z4") (pin "4") (pinfunction "3_4") (pintype "bidirectional"))
    )
    (net (code "297") (name "unconnected-(Z5-2-Pad3)") (class "Default")
      (node (ref "Z5") (pin "3") (pinfunction "2_3") (pintype "bidirectional"))
    )
    (net (code "298") (name "unconnected-(Z5-3-Pad4)") (class "Default")
      (node (ref "Z5") (pin "4") (pinfunction "3_4") (pintype "bidirectional"))
    )
    (net (code "299") (name "unconnected-(Z6-2-Pad3)") (class "Default")
      (node (ref "Z6") (pin "3") (pinfunction "2_3") (pintype "bidirectional"))
    )
    (net (code "300") (name "unconnected-(Z6-3-Pad4)") (class "Default")
      (node (ref "Z6") (pin "4") (pinfunction "3_4") (pintype "bidirectional"))
    )
    (net (code "301") (name "unconnected-(Z7-2-Pad3)") (class "Default")
      (node (ref "Z7") (pin "3") (pinfunction "2_3") (pintype "bidirectional"))
    )
    (net (code "302") (name "unconnected-(Z7-3-Pad4)") (class "Default")
      (node (ref "Z7") (pin "4") (pinfunction "3_4") (pintype "bidirectional"))
    )
    (net (code "303") (name "unconnected-(Z8-2-Pad3)") (class "Default")
      (node (ref "Z8") (pin "3") (pinfunction "2_3") (pintype "bidirectional"))
    )
    (net (code "304") (name "unconnected-(Z8-3-Pad4)") (class "Default")
      (node (ref "Z8") (pin "4") (pinfunction "3_4") (pintype "bidirectional"))
    )
    (net (code "305") (name "unconnected-(Z9-2-Pad3)") (class "Default")
      (node (ref "Z9") (pin "3") (pinfunction "2_3") (pintype "bidirectional"))
    )
    (net (code "306") (name "unconnected-(Z9-3-Pad4)") (class "Default")
      (node (ref "Z9") (pin "4") (pinfunction "3_4") (pintype "bidirectional"))
    )
    (net (code "307") (name "unconnected-(Z10-2-Pad3)") (class "Default")
      (node (ref "Z10") (pin "3") (pinfunction "2_3") (pintype "bidirectional"))
    )
    (net (code "308") (name "unconnected-(Z10-3-Pad4)") (class "Default")
      (node (ref "Z10") (pin "4") (pinfunction "3_4") (pintype "bidirectional"))
    )
    (net (code "309") (name "unconnected-(Z11-2-Pad3)") (class "Default")
      (node (ref "Z11") (pin "3") (pinfunction "2_3") (pintype "bidirectional"))
    )
    (net (code "310") (name "unconnected-(Z11-3-Pad4)") (class "Default")
      (node (ref "Z11") (pin "4") (pinfunction "3_4") (pintype "bidirectional"))
    )
    (net (code "311") (name "unconnected-(Z12-2-Pad3)") (class "Default")
      (node (ref "Z12") (pin "3") (pinfunction "2_3") (pintype "bidirectional"))
    )
    (net (code "312") (name "unconnected-(Z12-3-Pad4)") (class "Default")
      (node (ref "Z12") (pin "4") (pinfunction "3_4") (pintype "bidirectional"))
    )
    (net (code "313") (name "unconnected-(Z13-2-Pad3)") (class "Default")
      (node (ref "Z13") (pin "3") (pinfunction "2_3") (pintype "bidirectional"))
    )
    (net (code "314") (name "unconnected-(Z13-3-Pad4)") (class "Default")
      (node (ref "Z13") (pin "4") (pinfunction "3_4") (pintype "bidirectional"))
    )
    (net (code "315") (name "unconnected-(Z14-2-Pad3)") (class "Default")
      (node (ref "Z14") (pin "3") (pinfunction "2_3") (pintype "bidirectional"))
    )
    (net (code "316") (name "unconnected-(Z14-3-Pad4)") (class "Default")
      (node (ref "Z14") (pin "4") (pinfunction "3_4") (pintype "bidirectional"))
    )
    (net (code "317") (name "unconnected-(Z15-2-Pad3)") (class "Default")
      (node (ref "Z15") (pin "3") (pinfunction "2_3") (pintype "bidirectional"))
    )
    (net (code "318") (name "unconnected-(Z15-3-Pad4)") (class "Default")
      (node (ref "Z15") (pin "4") (pinfunction "3_4") (pintype "bidirectional"))
    )
    (net (code "319") (name "unconnected-(Z16-2-Pad3)") (class "Default")
      (node (ref "Z16") (pin "3") (pinfunction "2_3") (pintype "bidirectional"))
    )
    (net (code "320") (name "unconnected-(Z16-3-Pad4)") (class "Default")
      (node (ref "Z16") (pin "4") (pinfunction "3_4") (pintype "bidirectional"))
    )
    (net (code "321") (name "unconnected-(Z17-2-Pad3)") (class "Default")
      (node (ref "Z17") (pin "3") (pinfunction "2_3") (pintype "bidirectional"))
    )
    (net (code "322") (name "unconnected-(Z17-3-Pad4)") (class "Default")
      (node (ref "Z17") (pin "4") (pinfunction "3_4") (pintype "bidirectional"))
    )
    (net (code "323") (name "unconnected-(Z18-2-Pad3)") (class "Default")
      (node (ref "Z18") (pin "3") (pinfunction "2_3") (pintype "bidirectional"))
    )
    (net (code "324") (name "unconnected-(Z18-3-Pad4)") (class "Default")
      (node (ref "Z18") (pin "4") (pinfunction "3_4") (pintype "bidirectional"))
    )
    (net (code "325") (name "unconnected-(Z19-2-Pad3)") (class "Default")
      (node (ref "Z19") (pin "3") (pinfunction "2_3") (pintype "bidirectional"))
    )
    (net (code "326") (name "unconnected-(Z19-3-Pad4)") (class "Default")
      (node (ref "Z19") (pin "4") (pinfunction "3_4") (pintype "bidirectional"))
    )
    (net (code "327") (name "unconnected-(Z20-2-Pad3)") (class "Default")
      (node (ref "Z20") (pin "3") (pinfunction "2_3") (pintype "bidirectional"))
    )
    (net (code "328") (name "unconnected-(Z20-3-Pad4)") (class "Default")
      (node (ref "Z20") (pin "4") (pinfunction "3_4") (pintype "bidirectional"))
    )
    (net (code "329") (name "unconnected-(Z21-2-Pad3)") (class "Default")
      (node (ref "Z21") (pin "3") (pinfunction "2_3") (pintype "bidirectional"))
    )
    (net (code "330") (name "unconnected-(Z21-3-Pad4)") (class "Default")
      (node (ref "Z21") (pin "4") (pinfunction "3_4") (pintype "bidirectional"))
    )
    (net (code "331") (name "unconnected-(Z22-2-Pad3)") (class "Default")
      (node (ref "Z22") (pin "3") (pinfunction "2_3") (pintype "bidirectional"))
    )
    (net (code "332") (name "unconnected-(Z22-3-Pad4)") (class "Default")
      (node (ref "Z22") (pin "4") (pinfunction "3_4") (pintype "bidirectional"))
    )
    (net (code "333") (name "unconnected-(Z23-2-Pad3)") (class "Default")
      (node (ref "Z23") (pin "3") (pinfunction "2_3") (pintype "bidirectional"))
    )
    (net (code "334") (name "unconnected-(Z23-3-Pad4)") (class "Default")
      (node (ref "Z23") (pin "4") (pinfunction "3_4") (pintype "bidirectional"))
    )
    (net (code "335") (name "unconnected-(Z24-2-Pad3)") (class "Default")
      (node (ref "Z24") (pin "3") (pinfunction "2_3") (pintype "bidirectional"))
    )
    (net (code "336") (name "unconnected-(Z24-3-Pad4)") (class "Default")
      (node (ref "Z24") (pin "4") (pinfunction "3_4") (pintype "bidirectional"))
    )
    (net (code "337") (name "unconnected-(Z25-2-Pad3)") (class "Default")
      (node (ref "Z25") (pin "3") (pinfunction "2_3") (pintype "bidirectional"))
    )
    (net (code "338") (name "unconnected-(Z25-3-Pad4)") (class "Default")
      (node (ref "Z25") (pin "4") (pinfunction "3_4") (pintype "bidirectional"))
    )
    (net (code "339") (name "unconnected-(Z26-2-Pad3)") (class "Default")
      (node (ref "Z26") (pin "3") (pinfunction "2_3") (pintype "bidirectional"))
    )
    (net (code "340") (name "unconnected-(Z26-3-Pad4)") (class "Default")
      (node (ref "Z26") (pin "4") (pinfunction "3_4") (pintype "bidirectional"))
    )
    (net (code "341") (name "unconnected-(Z27-2-Pad3)") (class "Default")
      (node (ref "Z27") (pin "3") (pinfunction "2_3") (pintype "bidirectional"))
    )
    (net (code "342") (name "unconnected-(Z27-3-Pad4)") (class "Default")
      (node (ref "Z27") (pin "4") (pinfunction "3_4") (pintype "bidirectional"))
    )
    (net (code "343") (name "unconnected-(Z28-2-Pad3)") (class "Default")
      (node (ref "Z28") (pin "3") (pinfunction "2_3") (pintype "bidirectional"))
    )
    (net (code "344") (name "unconnected-(Z28-3-Pad4)") (class "Default")
      (node (ref "Z28") (pin "4") (pinfunction "3_4") (pintype "bidirectional"))
    )
    (net (code "345") (name "~{CS_ADC}") (class "Default")
      (node (ref "J7") (pin "13") (pinfunction "13_13") (pintype "passive"))
    )
    (net (code "346") (name "~{CS_INPUT_NAND}") (class "Default")
      (node (ref "J8") (pin "10") (pinfunction "10_10") (pintype "passive"))
    )
    (net (code "347") (name "~{IMU_CS}") (class "Default")
      (node (ref "J8") (pin "03") (pinfunction "03_03") (pintype "passive"))
    )
    (net (code "348") (name "~{IMU_RST}") (class "Default")
      (node (ref "J8") (pin "01") (pinfunction "01_01") (pintype "passive"))
    )
    (net (code "349") (name "~{ISO_CS}") (class "Default")
      (node (ref "J8") (pin "28") (pinfunction "28_28") (pintype "passive"))
    )
    (net (code "350") (name "~{THERMOCOUPLE_CS}") (class "Default")
      (node (ref "J8") (pin "36") (pinfunction "36_36") (pintype "passive"))
    )
  )
)
